# StimFilterV1.net
KiCad netlist of a schematic drawn in EasyEDA Pro
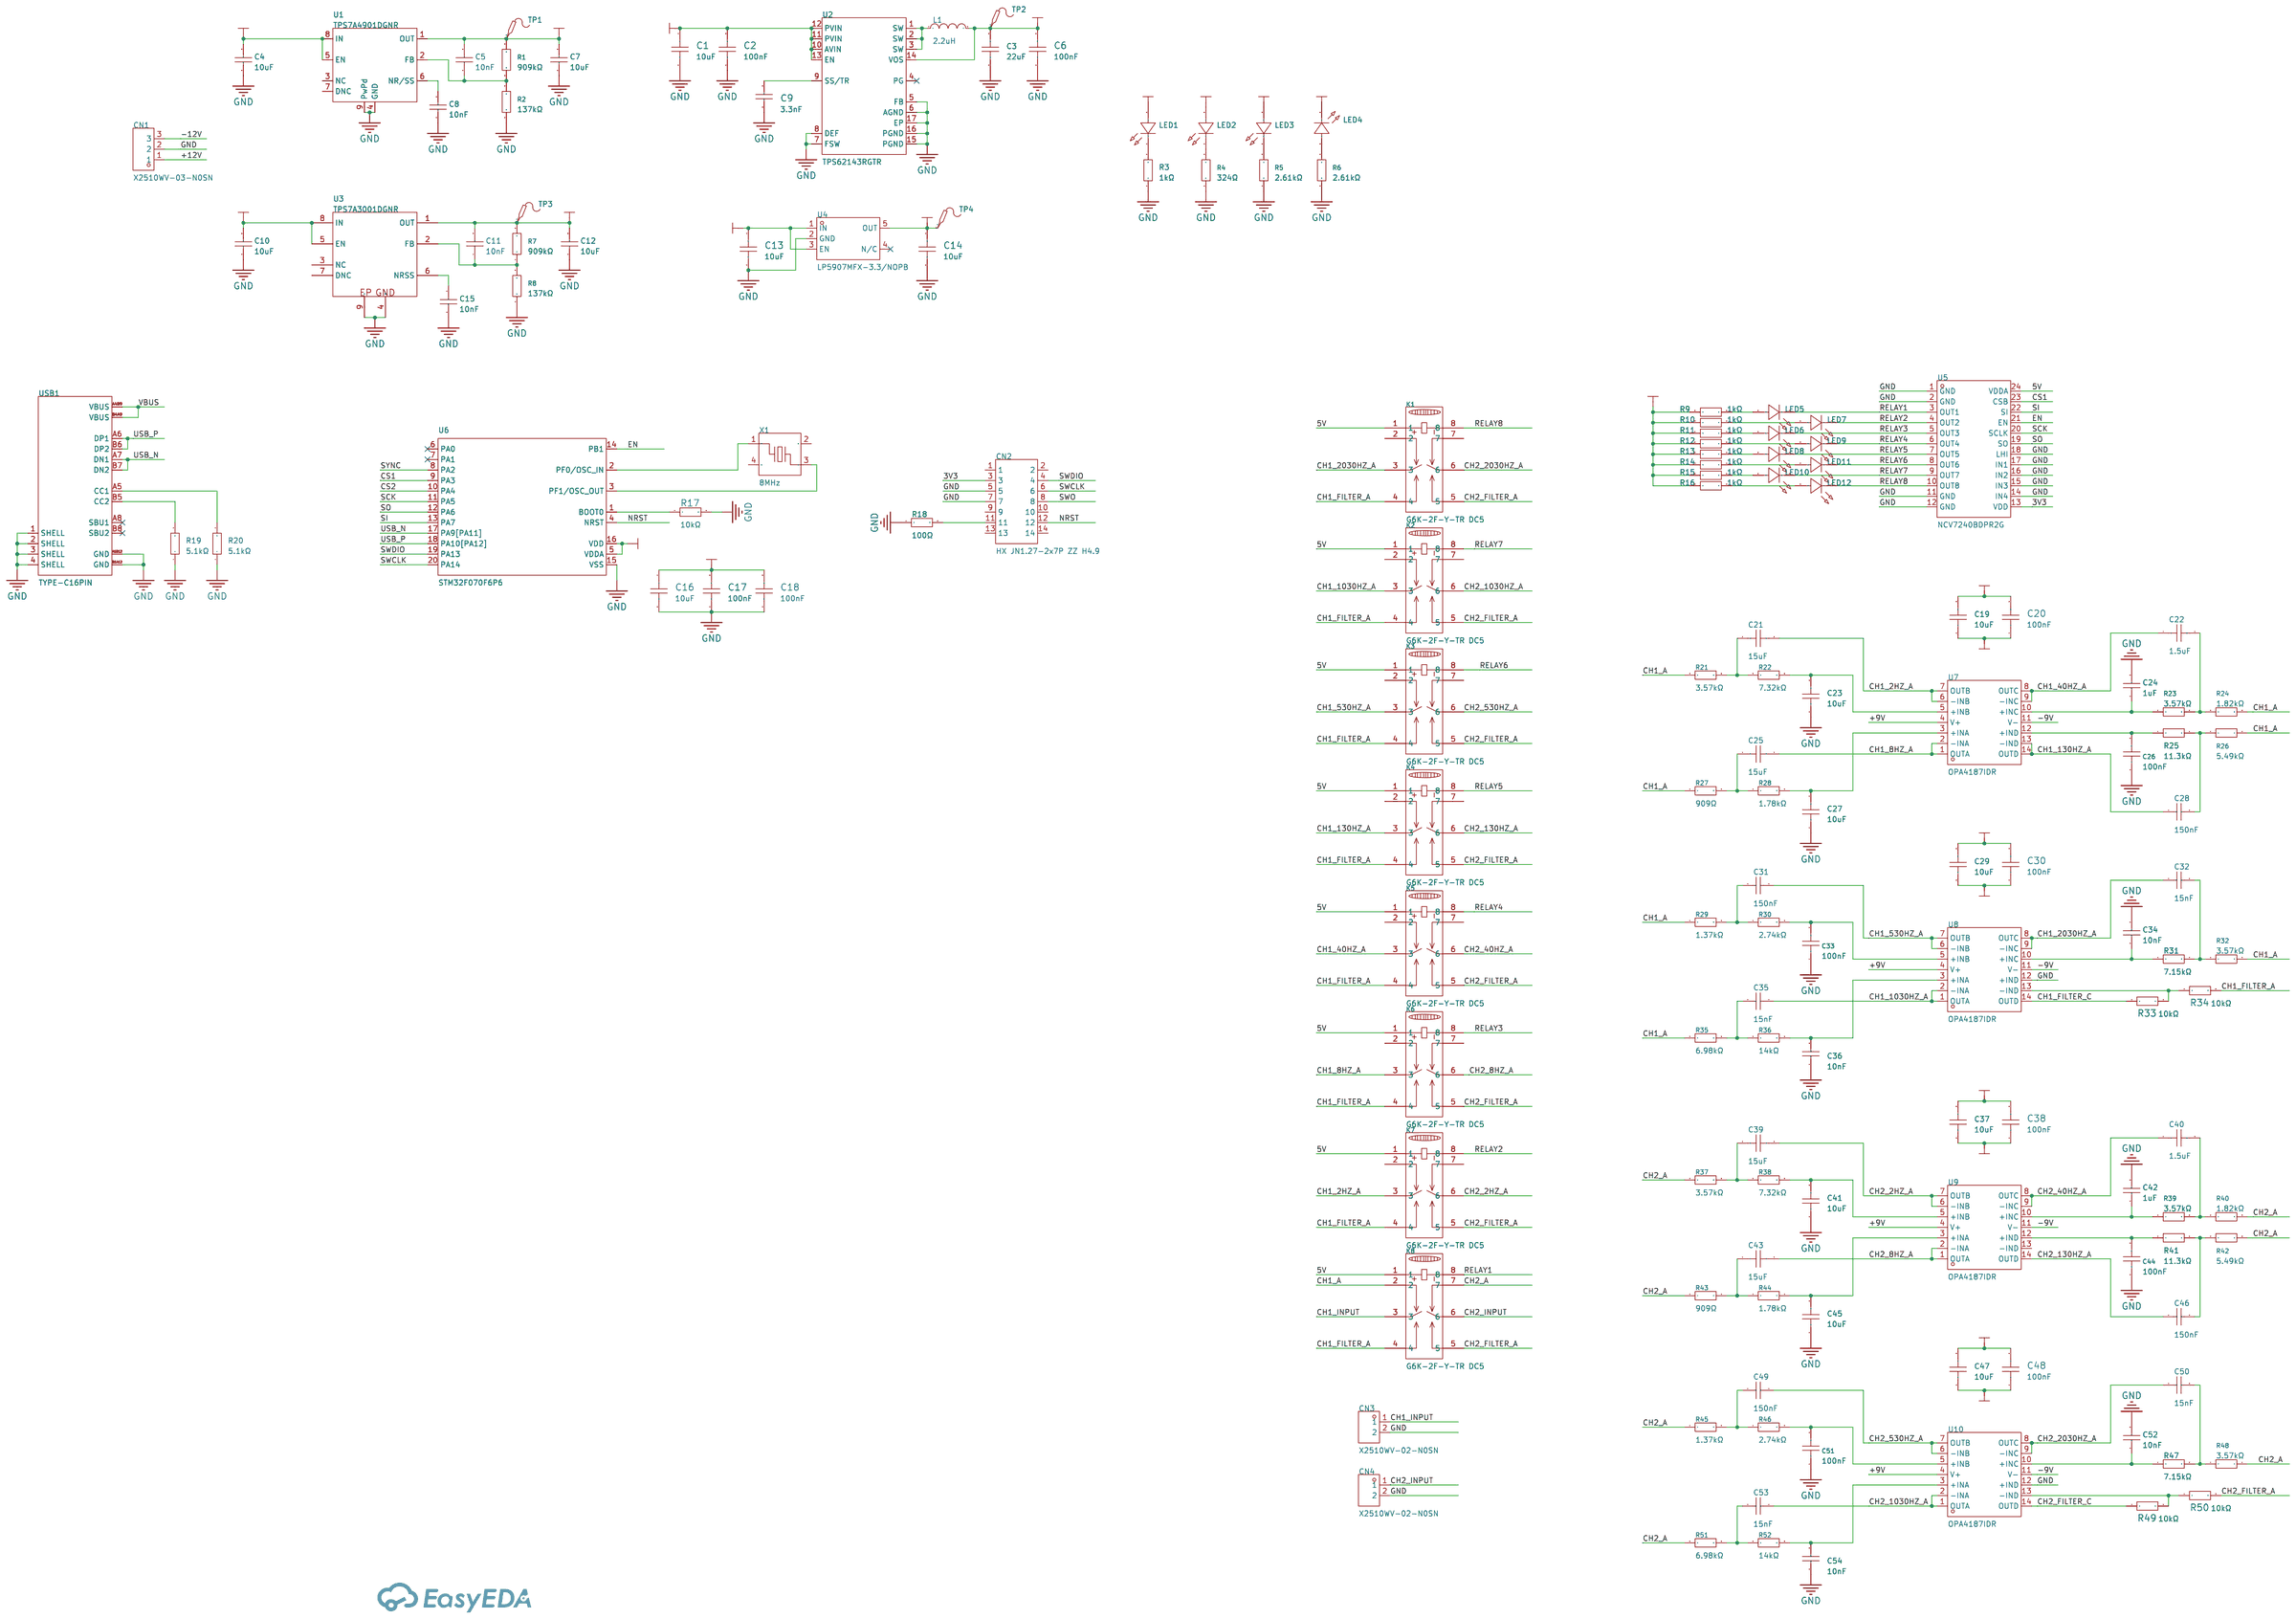
[diagram p0: P1]
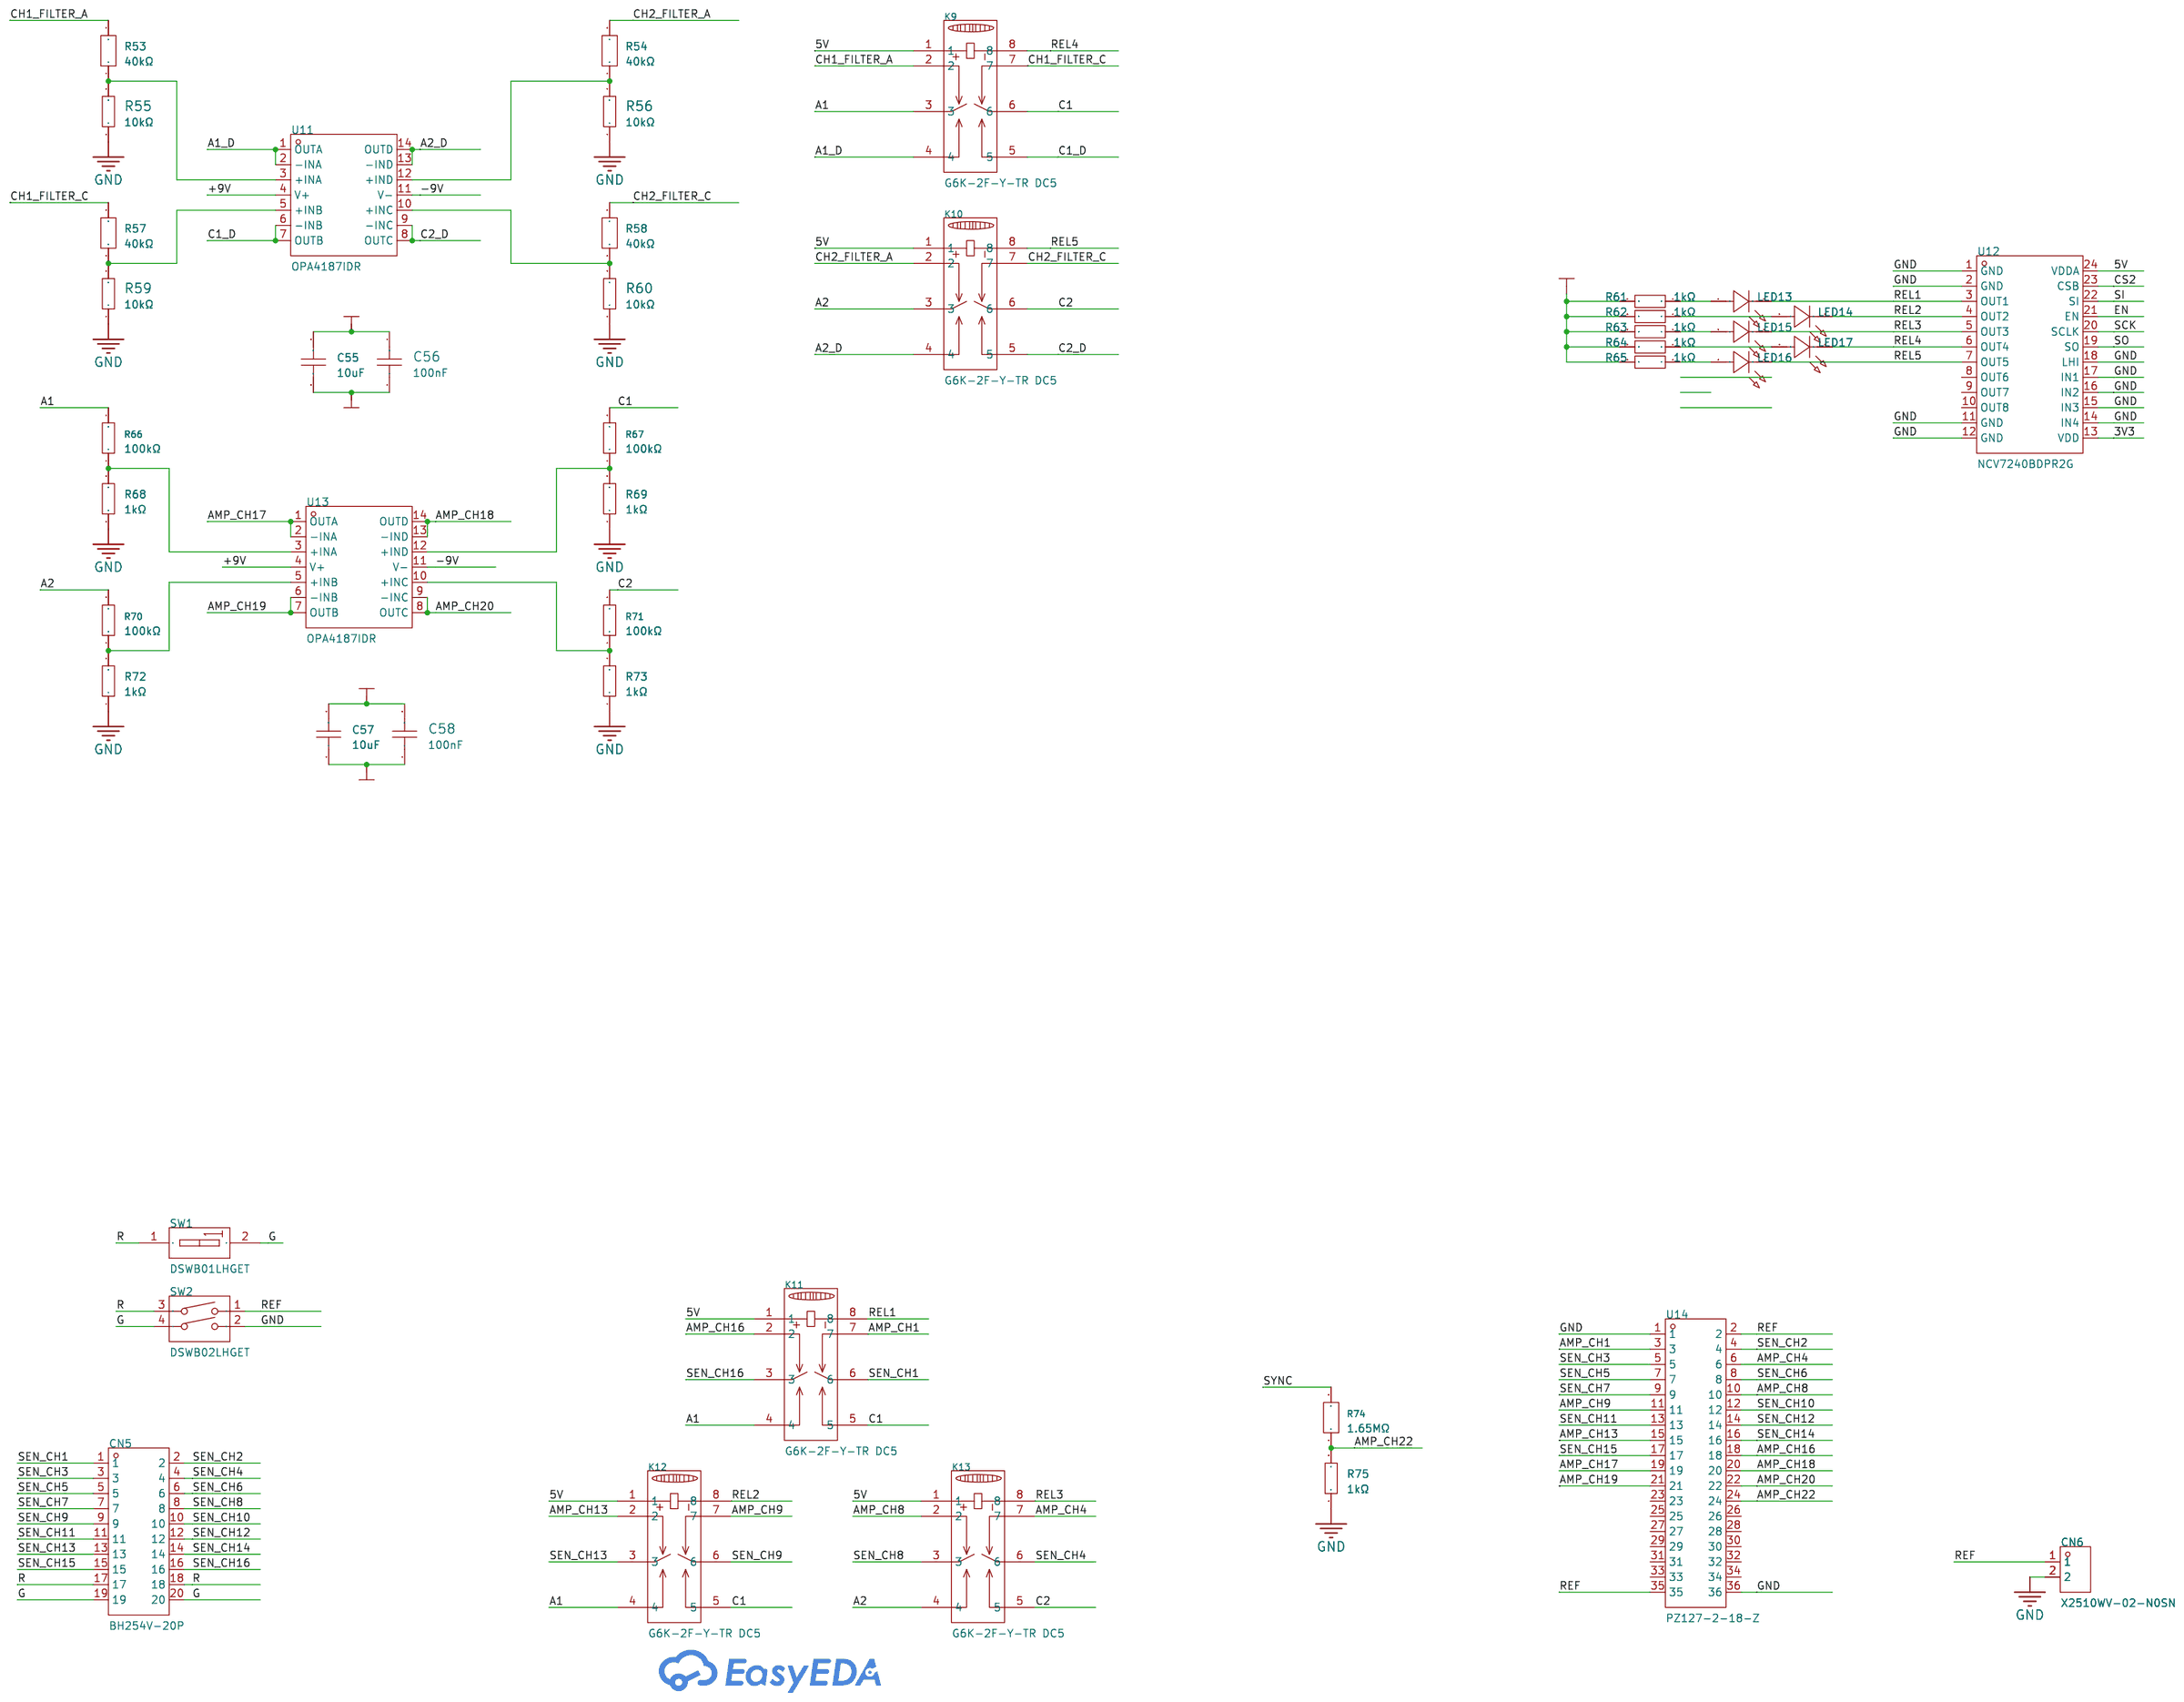
[diagram p1: P2]

(export (version "E")
  (design (tool "Eeschema 10.0.6"))
  (components
    (comp (ref "C1")
      (value "10uF")
      (footprint "easyedapro:C0603")
      (fields
        (field (name "Manufacturer Part") "GRM188R61E106KA73D")
        (field (name "Manufacturer") "muRata(村田)")
      )
      (libsource (lib "easyedapro") (part "GRM188R61E106KA73D"))
    )
    (comp (ref "C2")
      (value "100nF")
      (footprint "easyedapro:C0603")
      (fields
        (field (name "Manufacturer Part") "CC0603KRX7R9BB104")
        (field (name "Manufacturer") "YAGEO(国巨)")
      )
      (libsource (lib "easyedapro") (part "CC0603KRX7R9BB104"))
    )
    (comp (ref "C3")
      (value "22uF")
      (footprint "easyedapro:C0603")
      (fields
        (field (name "Manufacturer Part") "CL10A226MP8NUNE")
        (field (name "Manufacturer") "SAMSUNG(三星)")
      )
      (libsource (lib "easyedapro") (part "CL10A226MP8NUNE"))
    )
    (comp (ref "C4")
      (value "10uF")
      (footprint "easyedapro:C0805")
      (description "Capacitance:10uF Tolerance:±10% Tolerance:±10% Voltage Rating:10V Temperature Coefficient:X7R")
      (fields
        (field (name "Manufacturer Part") "CL21B106KPQNNNE")
        (field (name "Manufacturer") "SAMSUNG(三星)")
      )
      (libsource (lib "easyedapro") (part "CL21B106KPQNNNE"))
    )
    (comp (ref "C5")
      (value "10nF")
      (footprint "easyedapro:C0603")
      (description "Capacitance:10nF Tolerance:±10% Tolerance:±10% Voltage Rating:50V Temperature Coefficient:X7R")
      (fields
        (field (name "Manufacturer Part") "CL10B103KB8NNNC")
        (field (name "Manufacturer") "SAMSUNG(三星)")
      )
      (libsource (lib "easyedapro") (part "CL10B103KB8NNNC"))
    )
    (comp (ref "C6")
      (value "100nF")
      (footprint "easyedapro:C0603")
      (fields
        (field (name "Manufacturer Part") "CC0603KRX7R9BB104")
        (field (name "Manufacturer") "YAGEO(国巨)")
      )
      (libsource (lib "easyedapro") (part "CC0603KRX7R9BB104"))
    )
    (comp (ref "C7")
      (value "10uF")
      (footprint "easyedapro:C0805")
      (description "Capacitance:10uF Tolerance:±10% Tolerance:±10% Voltage Rating:10V Temperature Coefficient:X7R")
      (fields
        (field (name "Manufacturer Part") "CL21B106KPQNNNE")
        (field (name "Manufacturer") "SAMSUNG(三星)")
      )
      (libsource (lib "easyedapro") (part "CL21B106KPQNNNE"))
    )
    (comp (ref "C8")
      (value "10nF")
      (footprint "easyedapro:C0603")
      (description "Capacitance:10nF Tolerance:±10% Tolerance:±10% Voltage Rating:50V Temperature Coefficient:X7R")
      (fields
        (field (name "Manufacturer Part") "CL10B103KB8NNNC")
        (field (name "Manufacturer") "SAMSUNG(三星)")
      )
      (libsource (lib "easyedapro") (part "CL10B103KB8NNNC"))
    )
    (comp (ref "C9")
      (value "3.3nF")
      (footprint "easyedapro:C0603")
      (fields
        (field (name "Manufacturer Part") "CC0603KRX7R9BB332")
        (field (name "Manufacturer") "YAGEO(国巨)")
      )
      (libsource (lib "easyedapro") (part "CC0603KRX7R9BB332"))
    )
    (comp (ref "C10")
      (value "10uF")
      (footprint "easyedapro:C0805")
      (description "Capacitance:10uF Tolerance:±10% Tolerance:±10% Voltage Rating:10V Temperature Coefficient:X7R")
      (fields
        (field (name "Manufacturer Part") "CL21B106KPQNNNE")
        (field (name "Manufacturer") "SAMSUNG(三星)")
      )
      (libsource (lib "easyedapro") (part "CL21B106KPQNNNE"))
    )
    (comp (ref "C11")
      (value "10nF")
      (footprint "easyedapro:C0603")
      (description "Capacitance:10nF Tolerance:±10% Tolerance:±10% Voltage Rating:50V Temperature Coefficient:X7R")
      (fields
        (field (name "Manufacturer Part") "CL10B103KB8NNNC")
        (field (name "Manufacturer") "SAMSUNG(三星)")
      )
      (libsource (lib "easyedapro") (part "CL10B103KB8NNNC"))
    )
    (comp (ref "C12")
      (value "10uF")
      (footprint "easyedapro:C0805")
      (description "Capacitance:10uF Tolerance:±10% Tolerance:±10% Voltage Rating:10V Temperature Coefficient:X7R")
      (fields
        (field (name "Manufacturer Part") "CL21B106KPQNNNE")
        (field (name "Manufacturer") "SAMSUNG(三星)")
      )
      (libsource (lib "easyedapro") (part "CL21B106KPQNNNE"))
    )
    (comp (ref "C13")
      (value "10uF")
      (footprint "easyedapro:C0603")
      (fields
        (field (name "Manufacturer Part") "GRM188R61E106KA73D")
        (field (name "Manufacturer") "muRata(村田)")
      )
      (libsource (lib "easyedapro") (part "GRM188R61E106KA73D"))
    )
    (comp (ref "C14")
      (value "10uF")
      (footprint "easyedapro:C0603")
      (fields
        (field (name "Manufacturer Part") "GRM188R61E106KA73D")
        (field (name "Manufacturer") "muRata(村田)")
      )
      (libsource (lib "easyedapro") (part "GRM188R61E106KA73D"))
    )
    (comp (ref "C15")
      (value "10nF")
      (footprint "easyedapro:C0603")
      (description "Capacitance:10nF Tolerance:±10% Tolerance:±10% Voltage Rating:50V Temperature Coefficient:X7R")
      (fields
        (field (name "Manufacturer Part") "CL10B103KB8NNNC")
        (field (name "Manufacturer") "SAMSUNG(三星)")
      )
      (libsource (lib "easyedapro") (part "CL10B103KB8NNNC"))
    )
    (comp (ref "C16")
      (value "10uF")
      (footprint "easyedapro:C0603")
      (fields
        (field (name "Manufacturer Part") "GRM188R61E106KA73D")
        (field (name "Manufacturer") "muRata(村田)")
      )
      (libsource (lib "easyedapro") (part "GRM188R61E106KA73D"))
    )
    (comp (ref "C17")
      (value "100nF")
      (footprint "easyedapro:C0603")
      (fields
        (field (name "Manufacturer Part") "CC0603KRX7R9BB104")
        (field (name "Manufacturer") "YAGEO(国巨)")
      )
      (libsource (lib "easyedapro") (part "CC0603KRX7R9BB104"))
    )
    (comp (ref "C18")
      (value "100nF")
      (footprint "easyedapro:C0603")
      (fields
        (field (name "Manufacturer Part") "CC0603KRX7R9BB104")
        (field (name "Manufacturer") "YAGEO(国巨)")
      )
      (libsource (lib "easyedapro") (part "CC0603KRX7R9BB104"))
    )
    (comp (ref "C19")
      (value "10uF")
      (footprint "easyedapro:C0805")
      (description "Capacitance:10uF Tolerance:±10% Tolerance:±10% Voltage Rating:25V Temperature Coefficient:X5R")
      (fields
        (field (name "Manufacturer Part") "CL21A106KAYNNNE")
        (field (name "Manufacturer") "SAMSUNG(三星)")
      )
      (libsource (lib "easyedapro") (part "CL21A106KAYNNNE"))
    )
    (comp (ref "C20")
      (value "100nF")
      (footprint "easyedapro:C0603")
      (fields
        (field (name "Manufacturer Part") "CC0603KRX7R9BB104")
        (field (name "Manufacturer") "YAGEO(国巨)")
      )
      (libsource (lib "easyedapro") (part "CC0603KRX7R9BB104"))
    )
    (comp (ref "C21")
      (value "15uF")
      (footprint "easyedapro:C0603")
      (description "Capacitance:15uF Tolerance:±20% Tolerance:±20% Voltage Rating:6.3V Temperature Coefficient:X5R")
      (fields (field (name "Manufacturer Part") "C1608X5R0J156MT000E") (field (name "Manufacturer") "TDK"))
      (libsource (lib "easyedapro") (part "C1608X5R0J156MT000E"))
    )
    (comp (ref "C22")
      (value "1.5uF")
      (footprint "easyedapro:C0603")
      (description "Capacitance:1.5uF Tolerance:±10% Tolerance:±10% Voltage Rating:10V Temperature Coefficient:X7R")
      (fields (field (name "Manufacturer Part") "C1608X7R1A155KT000E") (field (name "Manufacturer") "TDK"))
      (libsource (lib "easyedapro") (part "C1608X7R1A155KT000E"))
    )
    (comp (ref "C23")
      (value "10uF")
      (footprint "easyedapro:C0603")
      (description "Capacitance:10uF Tolerance:±10% Tolerance:±10% Voltage Rating:10V Temperature Coefficient:X5R")
      (fields
        (field (name "Manufacturer Part") "CL10A106KP8NNNC")
        (field (name "Manufacturer") "SAMSUNG(三星)")
      )
      (libsource (lib "easyedapro") (part "CL10A106KP8NNNC"))
    )
    (comp (ref "C24")
      (value "1uF")
      (footprint "easyedapro:C0603")
      (description "Capacitance:1uF Tolerance:±10% Tolerance:±10% Voltage Rating:16V Temperature Coefficient:X5R")
      (fields
        (field (name "Manufacturer Part") "CL10A105KO8NNNC")
        (field (name "Manufacturer") "SAMSUNG(三星)")
      )
      (libsource (lib "easyedapro") (part "CL10A105KO8NNNC"))
    )
    (comp (ref "C25")
      (value "15uF")
      (footprint "easyedapro:C0603")
      (description "Capacitance:15uF Tolerance:±20% Tolerance:±20% Voltage Rating:6.3V Temperature Coefficient:X5R")
      (fields (field (name "Manufacturer Part") "C1608X5R0J156MT000E") (field (name "Manufacturer") "TDK"))
      (libsource (lib "easyedapro") (part "C1608X5R0J156MT000E"))
    )
    (comp (ref "C26")
      (value "100nF")
      (footprint "easyedapro:C0603")
      (description "Capacitance:100nF Tolerance:±10% Tolerance:±10% Voltage Rating:50V Temperature Coefficient:X7R")
      (fields
        (field (name "Manufacturer Part") "CL10B104KB8NNNC")
        (field (name "Manufacturer") "SAMSUNG(三星)")
      )
      (libsource (lib "easyedapro") (part "CL10B104KB8NNNC"))
    )
    (comp (ref "C27")
      (value "10uF")
      (footprint "easyedapro:C0603")
      (description "Capacitance:10uF Tolerance:±10% Tolerance:±10% Voltage Rating:10V Temperature Coefficient:X5R")
      (fields
        (field (name "Manufacturer Part") "CL10A106KP8NNNC")
        (field (name "Manufacturer") "SAMSUNG(三星)")
      )
      (libsource (lib "easyedapro") (part "CL10A106KP8NNNC"))
    )
    (comp (ref "C28")
      (value "150nF")
      (footprint "easyedapro:C0603")
      (description "Capacitance:150nF Tolerance:±10% Tolerance:±10% Voltage Rating:50V Temperature Coefficient:X7R")
      (fields (field (name "Manufacturer Part") "0603B154K500NT") (field (name "Manufacturer") "FH(风华)"))
      (libsource (lib "easyedapro") (part "0603B154K500NT"))
    )
    (comp (ref "C29")
      (value "10uF")
      (footprint "easyedapro:C0805")
      (description "Capacitance:10uF Tolerance:±10% Tolerance:±10% Voltage Rating:25V Temperature Coefficient:X5R")
      (fields
        (field (name "Manufacturer Part") "CL21A106KAYNNNE")
        (field (name "Manufacturer") "SAMSUNG(三星)")
      )
      (libsource (lib "easyedapro") (part "CL21A106KAYNNNE"))
    )
    (comp (ref "C30")
      (value "100nF")
      (footprint "easyedapro:C0603")
      (fields
        (field (name "Manufacturer Part") "CC0603KRX7R9BB104")
        (field (name "Manufacturer") "YAGEO(国巨)")
      )
      (libsource (lib "easyedapro") (part "CC0603KRX7R9BB104"))
    )
    (comp (ref "C31")
      (value "150nF")
      (footprint "easyedapro:C0603")
      (description "Capacitance:150nF Tolerance:±10% Tolerance:±10% Voltage Rating:50V Temperature Coefficient:X7R")
      (fields (field (name "Manufacturer Part") "0603B154K500NT") (field (name "Manufacturer") "FH(风华)"))
      (libsource (lib "easyedapro") (part "0603B154K500NT"))
    )
    (comp (ref "C32")
      (value "15nF")
      (footprint "easyedapro:C0603")
      (description "Capacitance:15nF Tolerance:±10% Tolerance:±10% Voltage Rating:50V Temperature Coefficient:X7R")
      (fields (field (name "Manufacturer Part") "0603B153K500NT") (field (name "Manufacturer") "FH(风华)"))
      (libsource (lib "easyedapro") (part "0603B153K500NT"))
    )
    (comp (ref "C33")
      (value "100nF")
      (footprint "easyedapro:C0603")
      (description "Capacitance:100nF Tolerance:±10% Tolerance:±10% Voltage Rating:50V Temperature Coefficient:X7R")
      (fields
        (field (name "Manufacturer Part") "CL10B104KB8NNNC")
        (field (name "Manufacturer") "SAMSUNG(三星)")
      )
      (libsource (lib "easyedapro") (part "CL10B104KB8NNNC"))
    )
    (comp (ref "C34")
      (value "10nF")
      (footprint "easyedapro:C0603")
      (description "Capacitance:10nF Tolerance:±10% Tolerance:±10% Voltage Rating:50V Temperature Coefficient:X7R")
      (fields
        (field (name "Manufacturer Part") "CL10B103KB8NNNC")
        (field (name "Manufacturer") "SAMSUNG(三星)")
      )
      (libsource (lib "easyedapro") (part "CL10B103KB8NNNC"))
    )
    (comp (ref "C35")
      (value "15nF")
      (footprint "easyedapro:C0603")
      (description "Capacitance:15nF Tolerance:±10% Tolerance:±10% Voltage Rating:50V Temperature Coefficient:X7R")
      (fields (field (name "Manufacturer Part") "0603B153K500NT") (field (name "Manufacturer") "FH(风华)"))
      (libsource (lib "easyedapro") (part "0603B153K500NT"))
    )
    (comp (ref "C36")
      (value "10nF")
      (footprint "easyedapro:C0603")
      (description "Capacitance:10nF Tolerance:±10% Tolerance:±10% Voltage Rating:50V Temperature Coefficient:X7R")
      (fields
        (field (name "Manufacturer Part") "CL10B103KB8NNNC")
        (field (name "Manufacturer") "SAMSUNG(三星)")
      )
      (libsource (lib "easyedapro") (part "CL10B103KB8NNNC"))
    )
    (comp (ref "C37")
      (value "10uF")
      (footprint "easyedapro:C0805")
      (description "Capacitance:10uF Tolerance:±10% Tolerance:±10% Voltage Rating:25V Temperature Coefficient:X5R")
      (fields
        (field (name "Manufacturer Part") "CL21A106KAYNNNE")
        (field (name "Manufacturer") "SAMSUNG(三星)")
      )
      (libsource (lib "easyedapro") (part "CL21A106KAYNNNE"))
    )
    (comp (ref "C38")
      (value "100nF")
      (footprint "easyedapro:C0603")
      (fields
        (field (name "Manufacturer Part") "CC0603KRX7R9BB104")
        (field (name "Manufacturer") "YAGEO(国巨)")
      )
      (libsource (lib "easyedapro") (part "CC0603KRX7R9BB104"))
    )
    (comp (ref "C39")
      (value "15uF")
      (footprint "easyedapro:C0603")
      (description "Capacitance:15uF Tolerance:±20% Tolerance:±20% Voltage Rating:6.3V Temperature Coefficient:X5R")
      (fields (field (name "Manufacturer Part") "C1608X5R0J156MT000E") (field (name "Manufacturer") "TDK"))
      (libsource (lib "easyedapro") (part "C1608X5R0J156MT000E"))
    )
    (comp (ref "C40")
      (value "1.5uF")
      (footprint "easyedapro:C0603")
      (description "Capacitance:1.5uF Tolerance:±10% Tolerance:±10% Voltage Rating:10V Temperature Coefficient:X7R")
      (fields (field (name "Manufacturer Part") "C1608X7R1A155KT000E") (field (name "Manufacturer") "TDK"))
      (libsource (lib "easyedapro") (part "C1608X7R1A155KT000E"))
    )
    (comp (ref "C41")
      (value "10uF")
      (footprint "easyedapro:C0603")
      (description "Capacitance:10uF Tolerance:±10% Tolerance:±10% Voltage Rating:10V Temperature Coefficient:X5R")
      (fields
        (field (name "Manufacturer Part") "CL10A106KP8NNNC")
        (field (name "Manufacturer") "SAMSUNG(三星)")
      )
      (libsource (lib "easyedapro") (part "CL10A106KP8NNNC"))
    )
    (comp (ref "C42")
      (value "1uF")
      (footprint "easyedapro:C0603")
      (description "Capacitance:1uF Tolerance:±10% Tolerance:±10% Voltage Rating:16V Temperature Coefficient:X5R")
      (fields
        (field (name "Manufacturer Part") "CL10A105KO8NNNC")
        (field (name "Manufacturer") "SAMSUNG(三星)")
      )
      (libsource (lib "easyedapro") (part "CL10A105KO8NNNC"))
    )
    (comp (ref "C43")
      (value "15uF")
      (footprint "easyedapro:C0603")
      (description "Capacitance:15uF Tolerance:±20% Tolerance:±20% Voltage Rating:6.3V Temperature Coefficient:X5R")
      (fields (field (name "Manufacturer Part") "C1608X5R0J156MT000E") (field (name "Manufacturer") "TDK"))
      (libsource (lib "easyedapro") (part "C1608X5R0J156MT000E"))
    )
    (comp (ref "C44")
      (value "100nF")
      (footprint "easyedapro:C0603")
      (description "Capacitance:100nF Tolerance:±10% Tolerance:±10% Voltage Rating:50V Temperature Coefficient:X7R")
      (fields
        (field (name "Manufacturer Part") "CL10B104KB8NNNC")
        (field (name "Manufacturer") "SAMSUNG(三星)")
      )
      (libsource (lib "easyedapro") (part "CL10B104KB8NNNC"))
    )
    (comp (ref "C45")
      (value "10uF")
      (footprint "easyedapro:C0603")
      (description "Capacitance:10uF Tolerance:±10% Tolerance:±10% Voltage Rating:10V Temperature Coefficient:X5R")
      (fields
        (field (name "Manufacturer Part") "CL10A106KP8NNNC")
        (field (name "Manufacturer") "SAMSUNG(三星)")
      )
      (libsource (lib "easyedapro") (part "CL10A106KP8NNNC"))
    )
    (comp (ref "C46")
      (value "150nF")
      (footprint "easyedapro:C0603")
      (description "Capacitance:150nF Tolerance:±10% Tolerance:±10% Voltage Rating:50V Temperature Coefficient:X7R")
      (fields (field (name "Manufacturer Part") "0603B154K500NT") (field (name "Manufacturer") "FH(风华)"))
      (libsource (lib "easyedapro") (part "0603B154K500NT"))
    )
    (comp (ref "C47")
      (value "10uF")
      (footprint "easyedapro:C0805")
      (description "Capacitance:10uF Tolerance:±10% Tolerance:±10% Voltage Rating:25V Temperature Coefficient:X5R")
      (fields
        (field (name "Manufacturer Part") "CL21A106KAYNNNE")
        (field (name "Manufacturer") "SAMSUNG(三星)")
      )
      (libsource (lib "easyedapro") (part "CL21A106KAYNNNE"))
    )
    (comp (ref "C48")
      (value "100nF")
      (footprint "easyedapro:C0603")
      (fields
        (field (name "Manufacturer Part") "CC0603KRX7R9BB104")
        (field (name "Manufacturer") "YAGEO(国巨)")
      )
      (libsource (lib "easyedapro") (part "CC0603KRX7R9BB104"))
    )
    (comp (ref "C49")
      (value "150nF")
      (footprint "easyedapro:C0603")
      (description "Capacitance:150nF Tolerance:±10% Tolerance:±10% Voltage Rating:50V Temperature Coefficient:X7R")
      (fields (field (name "Manufacturer Part") "0603B154K500NT") (field (name "Manufacturer") "FH(风华)"))
      (libsource (lib "easyedapro") (part "0603B154K500NT"))
    )
    (comp (ref "C50")
      (value "15nF")
      (footprint "easyedapro:C0603")
      (description "Capacitance:15nF Tolerance:±10% Tolerance:±10% Voltage Rating:50V Temperature Coefficient:X7R")
      (fields (field (name "Manufacturer Part") "0603B153K500NT") (field (name "Manufacturer") "FH(风华)"))
      (libsource (lib "easyedapro") (part "0603B153K500NT"))
    )
    (comp (ref "C51")
      (value "100nF")
      (footprint "easyedapro:C0603")
      (description "Capacitance:100nF Tolerance:±10% Tolerance:±10% Voltage Rating:50V Temperature Coefficient:X7R")
      (fields
        (field (name "Manufacturer Part") "CL10B104KB8NNNC")
        (field (name "Manufacturer") "SAMSUNG(三星)")
      )
      (libsource (lib "easyedapro") (part "CL10B104KB8NNNC"))
    )
    (comp (ref "C52")
      (value "10nF")
      (footprint "easyedapro:C0603")
      (description "Capacitance:10nF Tolerance:±10% Tolerance:±10% Voltage Rating:50V Temperature Coefficient:X7R")
      (fields
        (field (name "Manufacturer Part") "CL10B103KB8NNNC")
        (field (name "Manufacturer") "SAMSUNG(三星)")
      )
      (libsource (lib "easyedapro") (part "CL10B103KB8NNNC"))
    )
    (comp (ref "C53")
      (value "15nF")
      (footprint "easyedapro:C0603")
      (description "Capacitance:15nF Tolerance:±10% Tolerance:±10% Voltage Rating:50V Temperature Coefficient:X7R")
      (fields (field (name "Manufacturer Part") "0603B153K500NT") (field (name "Manufacturer") "FH(风华)"))
      (libsource (lib "easyedapro") (part "0603B153K500NT"))
    )
    (comp (ref "C54")
      (value "10nF")
      (footprint "easyedapro:C0603")
      (description "Capacitance:10nF Tolerance:±10% Tolerance:±10% Voltage Rating:50V Temperature Coefficient:X7R")
      (fields
        (field (name "Manufacturer Part") "CL10B103KB8NNNC")
        (field (name "Manufacturer") "SAMSUNG(三星)")
      )
      (libsource (lib "easyedapro") (part "CL10B103KB8NNNC"))
    )
    (comp (ref "CN1")
      (value "X2510WV-03-N0SN")
      (footprint "easyedapro:CONN-TH_3P-X2510WV-0X-N0SN")
      (fields (field (name "Manufacturer") "XKB Connection(中国星坤)"))
      (libsource (lib "easyedapro") (part "X2510WV-03-N0SN"))
    )
    (comp (ref "CN2")
      (value "HX JN1.27-2x7P ZZ H4.9")
      (footprint "easyedapro:IDC-TH_14P-P1.27_C42455940")
      (fields (field (name "Manufacturer") "hanxia(韩下)"))
      (libsource (lib "easyedapro") (part "HX JN1.27-2X7P ZZ H4.9"))
    )
    (comp (ref "CN3")
      (value "X2510WV-02-N0SN")
      (footprint "easyedapro:CONN-TH_2P-X2510WV-02-N0SN")
      (fields (field (name "Manufacturer") "XKB Connection(中国星坤)"))
      (libsource (lib "easyedapro") (part "X2510WV-02-N0SN"))
    )
    (comp (ref "CN4")
      (value "X2510WV-02-N0SN")
      (footprint "easyedapro:CONN-TH_2P-X2510WV-02-N0SN")
      (fields (field (name "Manufacturer") "XKB Connection(中国星坤)"))
      (libsource (lib "easyedapro") (part "X2510WV-02-N0SN"))
    )
    (comp (ref "K1")
      (value "G6K-2F-Y-TR DC5")
      (footprint "easyedapro:RELAY-SMD_G6K-2F-X-XX")
      (fields (field (name "Manufacturer") "OMRON(欧姆龙)"))
      (libsource (lib "easyedapro") (part "G6K-2F-Y-DC5"))
    )
    (comp (ref "K2")
      (value "G6K-2F-Y-TR DC5")
      (footprint "easyedapro:RELAY-SMD_G6K-2F-X-XX")
      (fields (field (name "Manufacturer") "OMRON(欧姆龙)"))
      (libsource (lib "easyedapro") (part "G6K-2F-Y-DC5"))
    )
    (comp (ref "K3")
      (value "G6K-2F-Y-TR DC5")
      (footprint "easyedapro:RELAY-SMD_G6K-2F-X-XX")
      (fields (field (name "Manufacturer") "OMRON(欧姆龙)"))
      (libsource (lib "easyedapro") (part "G6K-2F-Y-DC5"))
    )
    (comp (ref "K4")
      (value "G6K-2F-Y-TR DC5")
      (footprint "easyedapro:RELAY-SMD_G6K-2F-X-XX")
      (fields (field (name "Manufacturer") "OMRON(欧姆龙)"))
      (libsource (lib "easyedapro") (part "G6K-2F-Y-DC5"))
    )
    (comp (ref "K5")
      (value "G6K-2F-Y-TR DC5")
      (footprint "easyedapro:RELAY-SMD_G6K-2F-X-XX")
      (fields (field (name "Manufacturer") "OMRON(欧姆龙)"))
      (libsource (lib "easyedapro") (part "G6K-2F-Y-DC5"))
    )
    (comp (ref "K6")
      (value "G6K-2F-Y-TR DC5")
      (footprint "easyedapro:RELAY-SMD_G6K-2F-X-XX")
      (fields (field (name "Manufacturer") "OMRON(欧姆龙)"))
      (libsource (lib "easyedapro") (part "G6K-2F-Y-DC5"))
    )
    (comp (ref "K7")
      (value "G6K-2F-Y-TR DC5")
      (footprint "easyedapro:RELAY-SMD_G6K-2F-X-XX")
      (fields (field (name "Manufacturer") "OMRON(欧姆龙)"))
      (libsource (lib "easyedapro") (part "G6K-2F-Y-DC5"))
    )
    (comp (ref "K8")
      (value "G6K-2F-Y-TR DC5")
      (footprint "easyedapro:RELAY-SMD_G6K-2F-X-XX")
      (fields (field (name "Manufacturer") "OMRON(欧姆龙)"))
      (libsource (lib "easyedapro") (part "G6K-2F-Y-DC5"))
    )
    (comp (ref "L1")
      (value "2.2uH")
      (footprint "easyedapro:L0806")
      (fields (field (name "Manufacturer Part") "TFM201610ALM-2R2MTAA") (field (name "Manufacturer") "TDK"))
      (libsource (lib "easyedapro") (part "TFM201610ALM-2R2MTAA"))
    )
    (comp (ref "LED1")
      (value "A-SP192DGHC-C01-4T")
      (footprint "easyedapro:LED0603-FD")
      (fields (field (name "Manufacturer") "Amicc(欧密格光电)"))
      (libsource (lib "easyedapro") (part "A-SP192DGHC-C01-4T"))
    )
    (comp (ref "LED2")
      (value "A-SP192DGHC-C01-4T")
      (footprint "easyedapro:LED0603-FD")
      (fields (field (name "Manufacturer") "Amicc(欧密格光电)"))
      (libsource (lib "easyedapro") (part "A-SP192DGHC-C01-4T"))
    )
    (comp (ref "LED3")
      (value "A-SP192DGHC-C01-4T")
      (footprint "easyedapro:LED0603-FD")
      (fields (field (name "Manufacturer") "Amicc(欧密格光电)"))
      (libsource (lib "easyedapro") (part "A-SP192DGHC-C01-4T"))
    )
    (comp (ref "LED4")
      (value "A-SP192DGHC-C01-4T")
      (footprint "easyedapro:LED0603-FD")
      (fields (field (name "Manufacturer") "Amicc(欧密格光电)"))
      (libsource (lib "easyedapro") (part "A-SP192DGHC-C01-4T"))
    )
    (comp (ref "LED5")
      (value "A-SP192DGHC-C01-4T")
      (footprint "easyedapro:LED0603-FD")
      (fields (field (name "Manufacturer") "Amicc(欧密格光电)"))
      (libsource (lib "easyedapro") (part "A-SP192DGHC-C01-4T"))
    )
    (comp (ref "LED6")
      (value "A-SP192DGHC-C01-4T")
      (footprint "easyedapro:LED0603-FD")
      (fields (field (name "Manufacturer") "Amicc(欧密格光电)"))
      (libsource (lib "easyedapro") (part "A-SP192DGHC-C01-4T"))
    )
    (comp (ref "LED7")
      (value "A-SP192DGHC-C01-4T")
      (footprint "easyedapro:LED0603-FD")
      (fields (field (name "Manufacturer") "Amicc(欧密格光电)"))
      (libsource (lib "easyedapro") (part "A-SP192DGHC-C01-4T"))
    )
    (comp (ref "LED8")
      (value "A-SP192DGHC-C01-4T")
      (footprint "easyedapro:LED0603-FD")
      (fields (field (name "Manufacturer") "Amicc(欧密格光电)"))
      (libsource (lib "easyedapro") (part "A-SP192DGHC-C01-4T"))
    )
    (comp (ref "LED9")
      (value "A-SP192DGHC-C01-4T")
      (footprint "easyedapro:LED0603-FD")
      (fields (field (name "Manufacturer") "Amicc(欧密格光电)"))
      (libsource (lib "easyedapro") (part "A-SP192DGHC-C01-4T"))
    )
    (comp (ref "LED10")
      (value "A-SP192DGHC-C01-4T")
      (footprint "easyedapro:LED0603-FD")
      (fields (field (name "Manufacturer") "Amicc(欧密格光电)"))
      (libsource (lib "easyedapro") (part "A-SP192DGHC-C01-4T"))
    )
    (comp (ref "LED11")
      (value "A-SP192DGHC-C01-4T")
      (footprint "easyedapro:LED0603-FD")
      (fields (field (name "Manufacturer") "Amicc(欧密格光电)"))
      (libsource (lib "easyedapro") (part "A-SP192DGHC-C01-4T"))
    )
    (comp (ref "LED12")
      (value "A-SP192DGHC-C01-4T")
      (footprint "easyedapro:LED0603-FD")
      (fields (field (name "Manufacturer") "Amicc(欧密格光电)"))
      (libsource (lib "easyedapro") (part "A-SP192DGHC-C01-4T"))
    )
    (comp (ref "R1")
      (value "909kΩ")
      (footprint "easyedapro:R0603")
      (fields
        (field (name "Manufacturer Part") "0603WAF9093T5E")
        (field (name "Manufacturer") "UNI-ROYAL(厚声)")
      )
      (libsource (lib "easyedapro") (part "0603WAF9093T5E"))
    )
    (comp (ref "R2")
      (value "137kΩ")
      (footprint "easyedapro:R0603")
      (fields
        (field (name "Manufacturer Part") "0603WAF1373T5E")
        (field (name "Manufacturer") "UNI-ROYAL(厚声)")
      )
      (libsource (lib "easyedapro") (part "0603WAF1373T5E"))
    )
    (comp (ref "R3")
      (value "1kΩ")
      (footprint "easyedapro:R0603")
      (fields
        (field (name "Manufacturer Part") "0603WAF1001T5E")
        (field (name "Manufacturer") "UNI-ROYAL(厚声)")
      )
      (libsource (lib "easyedapro") (part "0603WAF1001T5E"))
    )
    (comp (ref "R4")
      (value "324Ω")
      (footprint "easyedapro:R0603")
      (fields (field (name "Manufacturer Part") "RTT033240FTP") (field (name "Manufacturer") "RALEC(旺诠)"))
      (libsource (lib "easyedapro") (part "RTT033240FTP"))
    )
    (comp (ref "R5")
      (value "2.61kΩ")
      (footprint "easyedapro:R0603")
      (fields
        (field (name "Manufacturer Part") "0603WAF2611T5E")
        (field (name "Manufacturer") "UNI-ROYAL(厚声)")
      )
      (libsource (lib "easyedapro") (part "0603WAF2611T5E"))
    )
    (comp (ref "R6")
      (value "2.61kΩ")
      (footprint "easyedapro:R0603")
      (fields
        (field (name "Manufacturer Part") "0603WAF2611T5E")
        (field (name "Manufacturer") "UNI-ROYAL(厚声)")
      )
      (libsource (lib "easyedapro") (part "0603WAF2611T5E"))
    )
    (comp (ref "R7")
      (value "909kΩ")
      (footprint "easyedapro:R0603")
      (fields
        (field (name "Manufacturer Part") "0603WAF9093T5E")
        (field (name "Manufacturer") "UNI-ROYAL(厚声)")
      )
      (libsource (lib "easyedapro") (part "0603WAF9093T5E"))
    )
    (comp (ref "R8")
      (value "137kΩ")
      (footprint "easyedapro:R0603")
      (fields
        (field (name "Manufacturer Part") "0603WAF1373T5E")
        (field (name "Manufacturer") "UNI-ROYAL(厚声)")
      )
      (libsource (lib "easyedapro") (part "0603WAF1373T5E"))
    )
    (comp (ref "R9")
      (value "1kΩ")
      (footprint "easyedapro:R0603")
      (fields
        (field (name "Manufacturer Part") "0603WAF1001T5E")
        (field (name "Manufacturer") "UNI-ROYAL(厚声)")
      )
      (libsource (lib "easyedapro") (part "0603WAF1001T5E"))
    )
    (comp (ref "R10")
      (value "1kΩ")
      (footprint "easyedapro:R0603")
      (fields
        (field (name "Manufacturer Part") "0603WAF1001T5E")
        (field (name "Manufacturer") "UNI-ROYAL(厚声)")
      )
      (libsource (lib "easyedapro") (part "0603WAF1001T5E"))
    )
    (comp (ref "R11")
      (value "1kΩ")
      (footprint "easyedapro:R0603")
      (fields
        (field (name "Manufacturer Part") "0603WAF1001T5E")
        (field (name "Manufacturer") "UNI-ROYAL(厚声)")
      )
      (libsource (lib "easyedapro") (part "0603WAF1001T5E"))
    )
    (comp (ref "R12")
      (value "1kΩ")
      (footprint "easyedapro:R0603")
      (fields
        (field (name "Manufacturer Part") "0603WAF1001T5E")
        (field (name "Manufacturer") "UNI-ROYAL(厚声)")
      )
      (libsource (lib "easyedapro") (part "0603WAF1001T5E"))
    )
    (comp (ref "R13")
      (value "1kΩ")
      (footprint "easyedapro:R0603")
      (fields
        (field (name "Manufacturer Part") "0603WAF1001T5E")
        (field (name "Manufacturer") "UNI-ROYAL(厚声)")
      )
      (libsource (lib "easyedapro") (part "0603WAF1001T5E"))
    )
    (comp (ref "R14")
      (value "1kΩ")
      (footprint "easyedapro:R0603")
      (fields
        (field (name "Manufacturer Part") "0603WAF1001T5E")
        (field (name "Manufacturer") "UNI-ROYAL(厚声)")
      )
      (libsource (lib "easyedapro") (part "0603WAF1001T5E"))
    )
    (comp (ref "R15")
      (value "1kΩ")
      (footprint "easyedapro:R0603")
      (fields
        (field (name "Manufacturer Part") "0603WAF1001T5E")
        (field (name "Manufacturer") "UNI-ROYAL(厚声)")
      )
      (libsource (lib "easyedapro") (part "0603WAF1001T5E"))
    )
    (comp (ref "R16")
      (value "1kΩ")
      (footprint "easyedapro:R0603")
      (fields
        (field (name "Manufacturer Part") "0603WAF1001T5E")
        (field (name "Manufacturer") "UNI-ROYAL(厚声)")
      )
      (libsource (lib "easyedapro") (part "0603WAF1001T5E"))
    )
    (comp (ref "R17")
      (value "10kΩ")
      (footprint "easyedapro:R0603")
      (fields
        (field (name "Manufacturer Part") "0603WAF1002T5E")
        (field (name "Manufacturer") "UNI-ROYAL(厚声)")
      )
      (libsource (lib "easyedapro") (part "0603WAF1002T5E"))
    )
    (comp (ref "R18")
      (value "100Ω")
      (footprint "easyedapro:R0402")
      (fields (field (name "Manufacturer Part") "RC0402FR-07100RL") (field (name "Manufacturer") "YAGEO(国巨)"))
      (libsource (lib "easyedapro") (part "RC0402FR-07100RL"))
    )
    (comp (ref "R19")
      (value "5.1kΩ")
      (footprint "easyedapro:R0603")
      (fields
        (field (name "Manufacturer Part") "0603WAF5101T5E")
        (field (name "Manufacturer") "UNI-ROYAL(厚声)")
      )
      (libsource (lib "easyedapro") (part "0603WAF5101T5E"))
    )
    (comp (ref "R20")
      (value "5.1kΩ")
      (footprint "easyedapro:R0603")
      (fields
        (field (name "Manufacturer Part") "0603WAF5101T5E")
        (field (name "Manufacturer") "UNI-ROYAL(厚声)")
      )
      (libsource (lib "easyedapro") (part "0603WAF5101T5E"))
    )
    (comp (ref "R21")
      (value "3.57kΩ")
      (footprint "easyedapro:R0603")
      (fields
        (field (name "Manufacturer Part") "0603WAF3571T5E")
        (field (name "Manufacturer") "UNI-ROYAL(厚声)")
      )
      (libsource (lib "easyedapro") (part "0603WAF3571T5E"))
    )
    (comp (ref "R22")
      (value "7.32kΩ")
      (footprint "easyedapro:R0603")
      (fields
        (field (name "Manufacturer Part") "0603WAF7321T5E")
        (field (name "Manufacturer") "UNI-ROYAL(厚声)")
      )
      (libsource (lib "easyedapro") (part "0603WAF7321T5E"))
    )
    (comp (ref "R23")
      (value "3.57kΩ")
      (footprint "easyedapro:R0603")
      (fields
        (field (name "Manufacturer Part") "0603WAF3571T5E")
        (field (name "Manufacturer") "UNI-ROYAL(厚声)")
      )
      (libsource (lib "easyedapro") (part "0603WAF3571T5E"))
    )
    (comp (ref "R24")
      (value "1.82kΩ")
      (footprint "easyedapro:R0603")
      (fields
        (field (name "Manufacturer Part") "0603WAF1821T5E")
        (field (name "Manufacturer") "UNI-ROYAL(厚声)")
      )
      (libsource (lib "easyedapro") (part "0603WAF1821T5E"))
    )
    (comp (ref "R25")
      (value "11.3kΩ")
      (footprint "easyedapro:R0603")
      (fields
        (field (name "Manufacturer Part") "0603WAF1132T5E")
        (field (name "Manufacturer") "UNI-ROYAL(厚声)")
      )
      (libsource (lib "easyedapro") (part "0603WAF1132T5E"))
    )
    (comp (ref "R26")
      (value "5.49kΩ")
      (footprint "easyedapro:R0603")
      (fields (field (name "Manufacturer Part") "RTT035491FTP") (field (name "Manufacturer") "RALEC(旺诠)"))
      (libsource (lib "easyedapro") (part "RTT035491FTP"))
    )
    (comp (ref "R27")
      (value "909Ω")
      (footprint "easyedapro:R0603")
      (fields (field (name "Manufacturer Part") "RTT039090FTP") (field (name "Manufacturer") "RALEC(旺诠)"))
      (libsource (lib "easyedapro") (part "RTT039090FTP"))
    )
    (comp (ref "R28")
      (value "1.78kΩ")
      (footprint "easyedapro:R0603")
      (fields (field (name "Manufacturer Part") "RTT031781FTP") (field (name "Manufacturer") "RALEC(旺诠)"))
      (libsource (lib "easyedapro") (part "RTT031781FTP"))
    )
    (comp (ref "R29")
      (value "1.37kΩ")
      (footprint "easyedapro:R0603")
      (fields
        (field (name "Manufacturer Part") "0603WAF1371T5E")
        (field (name "Manufacturer") "UNI-ROYAL(厚声)")
      )
      (libsource (lib "easyedapro") (part "0603WAF1371T5E"))
    )
    (comp (ref "R30")
      (value "2.74kΩ")
      (footprint "easyedapro:R0603")
      (fields
        (field (name "Manufacturer Part") "0603WAF2741T5E")
        (field (name "Manufacturer") "UNI-ROYAL(厚声)")
      )
      (libsource (lib "easyedapro") (part "0603WAF2741T5E"))
    )
    (comp (ref "R31")
      (value "7.15kΩ")
      (footprint "easyedapro:R0603")
      (fields
        (field (name "Manufacturer Part") "0603WAF7151T5E")
        (field (name "Manufacturer") "UNI-ROYAL(厚声)")
      )
      (libsource (lib "easyedapro") (part "0603WAF7151T5E"))
    )
    (comp (ref "R32")
      (value "3.57kΩ")
      (footprint "easyedapro:R0603")
      (fields
        (field (name "Manufacturer Part") "0603WAF3571T5E")
        (field (name "Manufacturer") "UNI-ROYAL(厚声)")
      )
      (libsource (lib "easyedapro") (part "0603WAF3571T5E"))
    )
    (comp (ref "R33")
      (value "10kΩ")
      (footprint "easyedapro:R0603")
      (fields
        (field (name "Manufacturer Part") "0603WAF1002T5E")
        (field (name "Manufacturer") "UNI-ROYAL(厚声)")
      )
      (libsource (lib "easyedapro") (part "0603WAF1002T5E"))
    )
    (comp (ref "R34")
      (value "10kΩ")
      (footprint "easyedapro:R0603")
      (fields
        (field (name "Manufacturer Part") "0603WAF1002T5E")
        (field (name "Manufacturer") "UNI-ROYAL(厚声)")
      )
      (libsource (lib "easyedapro") (part "0603WAF1002T5E"))
    )
    (comp (ref "R35")
      (value "6.98kΩ")
      (footprint "easyedapro:R0603")
      (fields
        (field (name "Manufacturer Part") "0603WAF6981T5E")
        (field (name "Manufacturer") "UNI-ROYAL(厚声)")
      )
      (libsource (lib "easyedapro") (part "0603WAF6981T5E"))
    )
    (comp (ref "R36")
      (value "14kΩ")
      (footprint "easyedapro:R0603")
      (fields
        (field (name "Manufacturer Part") "0603WAF1402T5E")
        (field (name "Manufacturer") "UNI-ROYAL(厚声)")
      )
      (libsource (lib "easyedapro") (part "0603WAF1402T5E"))
    )
    (comp (ref "R37")
      (value "3.57kΩ")
      (footprint "easyedapro:R0603")
      (fields
        (field (name "Manufacturer Part") "0603WAF3571T5E")
        (field (name "Manufacturer") "UNI-ROYAL(厚声)")
      )
      (libsource (lib "easyedapro") (part "0603WAF3571T5E"))
    )
    (comp (ref "R38")
      (value "7.32kΩ")
      (footprint "easyedapro:R0603")
      (fields
        (field (name "Manufacturer Part") "0603WAF7321T5E")
        (field (name "Manufacturer") "UNI-ROYAL(厚声)")
      )
      (libsource (lib "easyedapro") (part "0603WAF7321T5E"))
    )
    (comp (ref "R39")
      (value "3.57kΩ")
      (footprint "easyedapro:R0603")
      (fields
        (field (name "Manufacturer Part") "0603WAF3571T5E")
        (field (name "Manufacturer") "UNI-ROYAL(厚声)")
      )
      (libsource (lib "easyedapro") (part "0603WAF3571T5E"))
    )
    (comp (ref "R40")
      (value "1.82kΩ")
      (footprint "easyedapro:R0603")
      (fields
        (field (name "Manufacturer Part") "0603WAF1821T5E")
        (field (name "Manufacturer") "UNI-ROYAL(厚声)")
      )
      (libsource (lib "easyedapro") (part "0603WAF1821T5E"))
    )
    (comp (ref "R41")
      (value "11.3kΩ")
      (footprint "easyedapro:R0603")
      (fields
        (field (name "Manufacturer Part") "0603WAF1132T5E")
        (field (name "Manufacturer") "UNI-ROYAL(厚声)")
      )
      (libsource (lib "easyedapro") (part "0603WAF1132T5E"))
    )
    (comp (ref "R42")
      (value "5.49kΩ")
      (footprint "easyedapro:R0603")
      (fields (field (name "Manufacturer Part") "RTT035491FTP") (field (name "Manufacturer") "RALEC(旺诠)"))
      (libsource (lib "easyedapro") (part "RTT035491FTP"))
    )
    (comp (ref "R43")
      (value "909Ω")
      (footprint "easyedapro:R0603")
      (fields (field (name "Manufacturer Part") "RTT039090FTP") (field (name "Manufacturer") "RALEC(旺诠)"))
      (libsource (lib "easyedapro") (part "RTT039090FTP"))
    )
    (comp (ref "R44")
      (value "1.78kΩ")
      (footprint "easyedapro:R0603")
      (fields (field (name "Manufacturer Part") "RTT031781FTP") (field (name "Manufacturer") "RALEC(旺诠)"))
      (libsource (lib "easyedapro") (part "RTT031781FTP"))
    )
    (comp (ref "R45")
      (value "1.37kΩ")
      (footprint "easyedapro:R0603")
      (fields
        (field (name "Manufacturer Part") "0603WAF1371T5E")
        (field (name "Manufacturer") "UNI-ROYAL(厚声)")
      )
      (libsource (lib "easyedapro") (part "0603WAF1371T5E"))
    )
    (comp (ref "R46")
      (value "2.74kΩ")
      (footprint "easyedapro:R0603")
      (fields
        (field (name "Manufacturer Part") "0603WAF2741T5E")
        (field (name "Manufacturer") "UNI-ROYAL(厚声)")
      )
      (libsource (lib "easyedapro") (part "0603WAF2741T5E"))
    )
    (comp (ref "R47")
      (value "7.15kΩ")
      (footprint "easyedapro:R0603")
      (fields
        (field (name "Manufacturer Part") "0603WAF7151T5E")
        (field (name "Manufacturer") "UNI-ROYAL(厚声)")
      )
      (libsource (lib "easyedapro") (part "0603WAF7151T5E"))
    )
    (comp (ref "R48")
      (value "3.57kΩ")
      (footprint "easyedapro:R0603")
      (fields
        (field (name "Manufacturer Part") "0603WAF3571T5E")
        (field (name "Manufacturer") "UNI-ROYAL(厚声)")
      )
      (libsource (lib "easyedapro") (part "0603WAF3571T5E"))
    )
    (comp (ref "R49")
      (value "10kΩ")
      (footprint "easyedapro:R0603")
      (fields
        (field (name "Manufacturer Part") "0603WAF1002T5E")
        (field (name "Manufacturer") "UNI-ROYAL(厚声)")
      )
      (libsource (lib "easyedapro") (part "0603WAF1002T5E"))
    )
    (comp (ref "R50")
      (value "10kΩ")
      (footprint "easyedapro:R0603")
      (fields
        (field (name "Manufacturer Part") "0603WAF1002T5E")
        (field (name "Manufacturer") "UNI-ROYAL(厚声)")
      )
      (libsource (lib "easyedapro") (part "0603WAF1002T5E"))
    )
    (comp (ref "R51")
      (value "6.98kΩ")
      (footprint "easyedapro:R0603")
      (fields
        (field (name "Manufacturer Part") "0603WAF6981T5E")
        (field (name "Manufacturer") "UNI-ROYAL(厚声)")
      )
      (libsource (lib "easyedapro") (part "0603WAF6981T5E"))
    )
    (comp (ref "R52")
      (value "14kΩ")
      (footprint "easyedapro:R0603")
      (fields
        (field (name "Manufacturer Part") "0603WAF1402T5E")
        (field (name "Manufacturer") "UNI-ROYAL(厚声)")
      )
      (libsource (lib "easyedapro") (part "0603WAF1402T5E"))
    )
    (comp (ref "TP1")
      (value "~")
      (footprint "easyedapro:Test-Point-0.5mm")
      (description "Test Point 测试点")
      (libsource (lib "easyedapro") (part "Test-Point"))
    )
    (comp (ref "TP2")
      (value "~")
      (footprint "easyedapro:Test-Point-0.5mm")
      (description "Test Point 测试点")
      (libsource (lib "easyedapro") (part "Test-Point"))
    )
    (comp (ref "TP3")
      (value "~")
      (footprint "easyedapro:Test-Point-0.5mm")
      (description "Test Point 测试点")
      (libsource (lib "easyedapro") (part "Test-Point"))
    )
    (comp (ref "TP4")
      (value "~")
      (footprint "easyedapro:Test-Point-0.5mm")
      (description "Test Point 测试点")
      (libsource (lib "easyedapro") (part "Test-Point"))
    )
    (comp (ref "U1")
      (value "TPS7A4901DGNR")
      (footprint "easyedapro:HVSSOP-8_L3.0-W3.0-P0.65-LS4.9-BL-EP_DGN0008D")
      (fields (field (name "Manufacturer") "TI(德州仪器)"))
      (libsource (lib "easyedapro") (part "TPS7A4901DGNR"))
    )
    (comp (ref "U2")
      (value "TPS62143RGTR")
      (footprint "easyedapro:TQFN-16_L3.0-W3.0-P0.50-TL-EP1.7")
      (fields (field (name "Manufacturer") "TI(德州仪器)"))
      (libsource (lib "easyedapro") (part "TPS62143RGTR"))
    )
    (comp (ref "U3")
      (value "TPS7A3001DGNR")
      (footprint "easyedapro:HVSSOP-8_L3.0-W3.0-P0.65-LS4.9-BL-EP_DGN0008D")
      (fields (field (name "Manufacturer") "TI(德州仪器)"))
      (libsource (lib "easyedapro") (part "TPS7A3001DGNR"))
    )
    (comp (ref "U4")
      (value "LP5907MFX-3.3/NOPB")
      (footprint "easyedapro:SOT-23-5_L3.0-W1.7-P0.95-LS2.8-BR")
      (fields (field (name "Manufacturer") "TI(德州仪器)"))
      (libsource (lib "easyedapro") (part "LP5907MFX-3.3/NOPB"))
    )
    (comp (ref "U5")
      (value "NCV7240BDPR2G")
      (footprint "easyedapro:SSOP-24_L8.7-W3.9-P0.65-LS6.0-BL")
      (fields (field (name "Manufacturer") "onsemi(安森美)"))
      (libsource (lib "easyedapro") (part "NCV7240BDPR2G"))
    )
    (comp (ref "U6")
      (value "STM32F070F6P6")
      (footprint "easyedapro:TSSOP-20_L6.5-W4.4-P0.65-LS6.4-BL")
      (fields (field (name "Manufacturer") "ST(意法半导体)"))
      (libsource (lib "easyedapro") (part "STM32F070F6P6"))
    )
    (comp (ref "U7")
      (value "OPA4187IDR")
      (footprint "easyedapro:SOIC-14_L8.7-W3.9-P1.27-LS6.0-BL")
      (fields (field (name "Manufacturer") "TI(德州仪器)"))
      (libsource (lib "easyedapro") (part "OPA4187IDR"))
    )
    (comp (ref "U8")
      (value "OPA4187IDR")
      (footprint "easyedapro:SOIC-14_L8.7-W3.9-P1.27-LS6.0-BL")
      (fields (field (name "Manufacturer") "TI(德州仪器)"))
      (libsource (lib "easyedapro") (part "OPA4187IDR"))
    )
    (comp (ref "U9")
      (value "OPA4187IDR")
      (footprint "easyedapro:SOIC-14_L8.7-W3.9-P1.27-LS6.0-BL")
      (fields (field (name "Manufacturer") "TI(德州仪器)"))
      (libsource (lib "easyedapro") (part "OPA4187IDR"))
    )
    (comp (ref "U10")
      (value "OPA4187IDR")
      (footprint "easyedapro:SOIC-14_L8.7-W3.9-P1.27-LS6.0-BL")
      (fields (field (name "Manufacturer") "TI(德州仪器)"))
      (libsource (lib "easyedapro") (part "OPA4187IDR"))
    )
    (comp (ref "USB1")
      (value "TYPE-C16PIN")
      (footprint "easyedapro:USB-C-SMD_TYPE-C16PIN")
      (fields (field (name "Manufacturer") "SHOU HAN(首韩)"))
      (libsource (lib "easyedapro") (part "TYPE-C16PIN"))
    )
    (comp (ref "X1")
      (value "8MHz")
      (footprint "easyedapro:CRYSTAL-SMD_4P-L3.2-W2.5-BL")
      (fields
        (field (name "Manufacturer Part") "3225 8M 12PF 10PPM")
        (field (name "Manufacturer") "SOSET(索斯特)")
      )
      (libsource (lib "easyedapro") (part "3225 8M 12PF 10PPM"))
    )
    (comp (ref "C55")
      (value "10uF")
      (footprint "easyedapro:C0805")
      (description "Capacitance:10uF Tolerance:±10% Tolerance:±10% Voltage Rating:25V Temperature Coefficient:X5R")
      (fields
        (field (name "Manufacturer Part") "CL21A106KAYNNNE")
        (field (name "Manufacturer") "SAMSUNG(三星)")
      )
      (libsource (lib "easyedapro") (part "CL21A106KAYNNNE"))
    )
    (comp (ref "C56")
      (value "100nF")
      (footprint "easyedapro:C0603")
      (fields
        (field (name "Manufacturer Part") "CC0603KRX7R9BB104")
        (field (name "Manufacturer") "YAGEO(国巨)")
      )
      (libsource (lib "easyedapro") (part "CC0603KRX7R9BB104"))
    )
    (comp (ref "C57")
      (value "10uF")
      (footprint "easyedapro:C0805")
      (description "Capacitance:10uF Tolerance:±10% Tolerance:±10% Voltage Rating:25V Temperature Coefficient:X5R")
      (fields
        (field (name "Manufacturer Part") "CL21A106KAYNNNE")
        (field (name "Manufacturer") "SAMSUNG(三星)")
      )
      (libsource (lib "easyedapro") (part "CL21A106KAYNNNE"))
    )
    (comp (ref "C58")
      (value "100nF")
      (footprint "easyedapro:C0603")
      (fields
        (field (name "Manufacturer Part") "CC0603KRX7R9BB104")
        (field (name "Manufacturer") "YAGEO(国巨)")
      )
      (libsource (lib "easyedapro") (part "CC0603KRX7R9BB104"))
    )
    (comp (ref "CN5")
      (value "BH254V-20P")
      (footprint "easyedapro:CONN-TH_20P-P2.54_0702462001")
      (fields (field (name "Manufacturer") "XFCN(兴飞)"))
      (libsource (lib "easyedapro") (part "BH254V-20P"))
    )
    (comp (ref "CN6")
      (value "X2510WV-02-N0SN")
      (footprint "easyedapro:CONN-TH_2P-X2510WV-02-N0SN")
      (fields (field (name "Manufacturer") "XKB Connection(中国星坤)"))
      (libsource (lib "easyedapro") (part "X2510WV-02-N0SN"))
    )
    (comp (ref "K9")
      (value "G6K-2F-Y-TR DC5")
      (footprint "easyedapro:RELAY-SMD_G6K-2F-X-XX")
      (fields (field (name "Manufacturer") "OMRON(欧姆龙)"))
      (libsource (lib "easyedapro") (part "G6K-2F-Y-DC5"))
    )
    (comp (ref "K10")
      (value "G6K-2F-Y-TR DC5")
      (footprint "easyedapro:RELAY-SMD_G6K-2F-X-XX")
      (fields (field (name "Manufacturer") "OMRON(欧姆龙)"))
      (libsource (lib "easyedapro") (part "G6K-2F-Y-DC5"))
    )
    (comp (ref "K11")
      (value "G6K-2F-Y-TR DC5")
      (footprint "easyedapro:RELAY-SMD_G6K-2F-X-XX")
      (fields (field (name "Manufacturer") "OMRON(欧姆龙)"))
      (libsource (lib "easyedapro") (part "G6K-2F-Y-DC5"))
    )
    (comp (ref "K12")
      (value "G6K-2F-Y-TR DC5")
      (footprint "easyedapro:RELAY-SMD_G6K-2F-X-XX")
      (fields (field (name "Manufacturer") "OMRON(欧姆龙)"))
      (libsource (lib "easyedapro") (part "G6K-2F-Y-DC5"))
    )
    (comp (ref "K13")
      (value "G6K-2F-Y-TR DC5")
      (footprint "easyedapro:RELAY-SMD_G6K-2F-X-XX")
      (fields (field (name "Manufacturer") "OMRON(欧姆龙)"))
      (libsource (lib "easyedapro") (part "G6K-2F-Y-DC5"))
    )
    (comp (ref "LED13")
      (value "A-SP192DGHC-C01-4T")
      (footprint "easyedapro:LED0603-FD")
      (fields (field (name "Manufacturer") "Amicc(欧密格光电)"))
      (libsource (lib "easyedapro") (part "A-SP192DGHC-C01-4T"))
    )
    (comp (ref "LED14")
      (value "A-SP192DGHC-C01-4T")
      (footprint "easyedapro:LED0603-FD")
      (fields (field (name "Manufacturer") "Amicc(欧密格光电)"))
      (libsource (lib "easyedapro") (part "A-SP192DGHC-C01-4T"))
    )
    (comp (ref "LED15")
      (value "A-SP192DGHC-C01-4T")
      (footprint "easyedapro:LED0603-FD")
      (fields (field (name "Manufacturer") "Amicc(欧密格光电)"))
      (libsource (lib "easyedapro") (part "A-SP192DGHC-C01-4T"))
    )
    (comp (ref "LED16")
      (value "A-SP192DGHC-C01-4T")
      (footprint "easyedapro:LED0603-FD")
      (fields (field (name "Manufacturer") "Amicc(欧密格光电)"))
      (libsource (lib "easyedapro") (part "A-SP192DGHC-C01-4T"))
    )
    (comp (ref "LED17")
      (value "A-SP192DGHC-C01-4T")
      (footprint "easyedapro:LED0603-FD")
      (fields (field (name "Manufacturer") "Amicc(欧密格光电)"))
      (libsource (lib "easyedapro") (part "A-SP192DGHC-C01-4T"))
    )
    (comp (ref "R53")
      (value "40kΩ")
      (footprint "easyedapro:R0603")
      (fields (field (name "Manufacturer Part") "SCR0603F40K") (field (name "Manufacturer") "VO(翔胜)"))
      (libsource (lib "easyedapro") (part "SCR0603F40K"))
    )
    (comp (ref "R54")
      (value "40kΩ")
      (footprint "easyedapro:R0603")
      (fields (field (name "Manufacturer Part") "SCR0603F40K") (field (name "Manufacturer") "VO(翔胜)"))
      (libsource (lib "easyedapro") (part "SCR0603F40K"))
    )
    (comp (ref "R55")
      (value "10kΩ")
      (footprint "easyedapro:R0603")
      (fields
        (field (name "Manufacturer Part") "0603WAF1002T5E")
        (field (name "Manufacturer") "UNI-ROYAL(厚声)")
      )
      (libsource (lib "easyedapro") (part "0603WAF1002T5E"))
    )
    (comp (ref "R56")
      (value "10kΩ")
      (footprint "easyedapro:R0603")
      (fields
        (field (name "Manufacturer Part") "0603WAF1002T5E")
        (field (name "Manufacturer") "UNI-ROYAL(厚声)")
      )
      (libsource (lib "easyedapro") (part "0603WAF1002T5E"))
    )
    (comp (ref "R57")
      (value "40kΩ")
      (footprint "easyedapro:R0603")
      (fields (field (name "Manufacturer Part") "SCR0603F40K") (field (name "Manufacturer") "VO(翔胜)"))
      (libsource (lib "easyedapro") (part "SCR0603F40K"))
    )
    (comp (ref "R58")
      (value "40kΩ")
      (footprint "easyedapro:R0603")
      (fields (field (name "Manufacturer Part") "SCR0603F40K") (field (name "Manufacturer") "VO(翔胜)"))
      (libsource (lib "easyedapro") (part "SCR0603F40K"))
    )
    (comp (ref "R59")
      (value "10kΩ")
      (footprint "easyedapro:R0603")
      (fields
        (field (name "Manufacturer Part") "0603WAF1002T5E")
        (field (name "Manufacturer") "UNI-ROYAL(厚声)")
      )
      (libsource (lib "easyedapro") (part "0603WAF1002T5E"))
    )
    (comp (ref "R60")
      (value "10kΩ")
      (footprint "easyedapro:R0603")
      (fields
        (field (name "Manufacturer Part") "0603WAF1002T5E")
        (field (name "Manufacturer") "UNI-ROYAL(厚声)")
      )
      (libsource (lib "easyedapro") (part "0603WAF1002T5E"))
    )
    (comp (ref "R61")
      (value "1kΩ")
      (footprint "easyedapro:R0603")
      (fields
        (field (name "Manufacturer Part") "0603WAF1001T5E")
        (field (name "Manufacturer") "UNI-ROYAL(厚声)")
      )
      (libsource (lib "easyedapro") (part "0603WAF1001T5E"))
    )
    (comp (ref "R62")
      (value "1kΩ")
      (footprint "easyedapro:R0603")
      (fields
        (field (name "Manufacturer Part") "0603WAF1001T5E")
        (field (name "Manufacturer") "UNI-ROYAL(厚声)")
      )
      (libsource (lib "easyedapro") (part "0603WAF1001T5E"))
    )
    (comp (ref "R63")
      (value "1kΩ")
      (footprint "easyedapro:R0603")
      (fields
        (field (name "Manufacturer Part") "0603WAF1001T5E")
        (field (name "Manufacturer") "UNI-ROYAL(厚声)")
      )
      (libsource (lib "easyedapro") (part "0603WAF1001T5E"))
    )
    (comp (ref "R64")
      (value "1kΩ")
      (footprint "easyedapro:R0603")
      (fields
        (field (name "Manufacturer Part") "0603WAF1001T5E")
        (field (name "Manufacturer") "UNI-ROYAL(厚声)")
      )
      (libsource (lib "easyedapro") (part "0603WAF1001T5E"))
    )
    (comp (ref "R65")
      (value "1kΩ")
      (footprint "easyedapro:R0603")
      (fields
        (field (name "Manufacturer Part") "0603WAF1001T5E")
        (field (name "Manufacturer") "UNI-ROYAL(厚声)")
      )
      (libsource (lib "easyedapro") (part "0603WAF1001T5E"))
    )
    (comp (ref "R66")
      (value "100kΩ")
      (footprint "easyedapro:R0603")
      (fields (field (name "Manufacturer Part") "RC0603FR-07100KL") (field (name "Manufacturer") "YAGEO(国巨)"))
      (libsource (lib "easyedapro") (part "RC0603FR-07100KL"))
    )
    (comp (ref "R67")
      (value "100kΩ")
      (footprint "easyedapro:R0603")
      (fields (field (name "Manufacturer Part") "RC0603FR-07100KL") (field (name "Manufacturer") "YAGEO(国巨)"))
      (libsource (lib "easyedapro") (part "RC0603FR-07100KL"))
    )
    (comp (ref "R68")
      (value "1kΩ")
      (footprint "easyedapro:R0603")
      (fields
        (field (name "Manufacturer Part") "0603WAF1001T5E")
        (field (name "Manufacturer") "UNI-ROYAL(厚声)")
      )
      (libsource (lib "easyedapro") (part "0603WAF1001T5E"))
    )
    (comp (ref "R69")
      (value "1kΩ")
      (footprint "easyedapro:R0603")
      (fields
        (field (name "Manufacturer Part") "0603WAF1001T5E")
        (field (name "Manufacturer") "UNI-ROYAL(厚声)")
      )
      (libsource (lib "easyedapro") (part "0603WAF1001T5E"))
    )
    (comp (ref "R70")
      (value "100kΩ")
      (footprint "easyedapro:R0603")
      (fields (field (name "Manufacturer Part") "RC0603FR-07100KL") (field (name "Manufacturer") "YAGEO(国巨)"))
      (libsource (lib "easyedapro") (part "RC0603FR-07100KL"))
    )
    (comp (ref "R71")
      (value "100kΩ")
      (footprint "easyedapro:R0603")
      (fields (field (name "Manufacturer Part") "RC0603FR-07100KL") (field (name "Manufacturer") "YAGEO(国巨)"))
      (libsource (lib "easyedapro") (part "RC0603FR-07100KL"))
    )
    (comp (ref "R72")
      (value "1kΩ")
      (footprint "easyedapro:R0603")
      (fields
        (field (name "Manufacturer Part") "0603WAF1001T5E")
        (field (name "Manufacturer") "UNI-ROYAL(厚声)")
      )
      (libsource (lib "easyedapro") (part "0603WAF1001T5E"))
    )
    (comp (ref "R73")
      (value "1kΩ")
      (footprint "easyedapro:R0603")
      (fields
        (field (name "Manufacturer Part") "0603WAF1001T5E")
        (field (name "Manufacturer") "UNI-ROYAL(厚声)")
      )
      (libsource (lib "easyedapro") (part "0603WAF1001T5E"))
    )
    (comp (ref "R74")
      (value "1.65MΩ")
      (footprint "easyedapro:R0603")
      (fields (field (name "Manufacturer Part") "RTT031654FTP") (field (name "Manufacturer") "RALEC(旺诠)"))
      (libsource (lib "easyedapro") (part "RTT031654FTP"))
    )
    (comp (ref "R75")
      (value "1kΩ")
      (footprint "easyedapro:R0603")
      (fields
        (field (name "Manufacturer Part") "0603WAF1001T5E")
        (field (name "Manufacturer") "UNI-ROYAL(厚声)")
      )
      (libsource (lib "easyedapro") (part "0603WAF1001T5E"))
    )
    (comp (ref "SW1")
      (value "DSWB01LHGET")
      (footprint "easyedapro:SW-TH_DSWB01LHGETR")
      (fields (field (name "Manufacturer") "HanElectricity(瀚源)"))
      (libsource (lib "easyedapro") (part "DSWB01LHGET_C25503176"))
    )
    (comp (ref "SW2")
      (value "DSWB02LHGET")
      (footprint "easyedapro:SW-TH_DSWB02LHGET")
      (description "Type:平拨,凸起式 Circuit:SPST Number of Positions:2Bit Lead Pitch:2.54mm Operating Life:- Color:Red")
      (fields (field (name "Manufacturer") "YE"))
      (libsource (lib "easyedapro") (part "DSWB02LHGET"))
    )
    (comp (ref "U11")
      (value "OPA4187IDR")
      (footprint "easyedapro:SOIC-14_L8.7-W3.9-P1.27-LS6.0-BL")
      (fields (field (name "Manufacturer") "TI(德州仪器)"))
      (libsource (lib "easyedapro") (part "OPA4187IDR"))
    )
    (comp (ref "U12")
      (value "NCV7240BDPR2G")
      (footprint "easyedapro:SSOP-24_L8.7-W3.9-P0.65-LS6.0-BL")
      (fields (field (name "Manufacturer") "onsemi(安森美)"))
      (libsource (lib "easyedapro") (part "NCV7240BDPR2G"))
    )
    (comp (ref "U13")
      (value "OPA4187IDR")
      (footprint "easyedapro:SOIC-14_L8.7-W3.9-P1.27-LS6.0-BL")
      (fields (field (name "Manufacturer") "TI(德州仪器)"))
      (libsource (lib "easyedapro") (part "OPA4187IDR"))
    )
    (comp (ref "U14")
      (value "PZ127-2-18-Z")
      (footprint "easyedapro:HDR-TH_36P-P1.27-V-M-R2-C18-S1.27")
      (fields (field (name "Manufacturer") "HCTL(华灿天禄)"))
      (libsource (lib "easyedapro") (part "PZ127-2-18-Z"))
    )
  )
  (nets
    (net (code "1") (name "+9V") (class "Default")
      (node (ref "C19") (pin "2") (pinfunction "2_2") (pintype "unspecified"))
      (node (ref "C20") (pin "2") (pinfunction "2_2") (pintype "input"))
      (node (ref "C29") (pin "2") (pinfunction "2_2") (pintype "unspecified"))
      (node (ref "C30") (pin "2") (pinfunction "2_2") (pintype "input"))
      (node (ref "C37") (pin "2") (pinfunction "2_2") (pintype "unspecified"))
      (node (ref "C38") (pin "2") (pinfunction "2_2") (pintype "input"))
      (node (ref "C47") (pin "2") (pinfunction "2_2") (pintype "unspecified"))
      (node (ref "C48") (pin "2") (pinfunction "2_2") (pintype "input"))
      (node (ref "C5") (pin "2") (pinfunction "2_2") (pintype "input"))
      (node (ref "C55") (pin "2") (pinfunction "2_2") (pintype "unspecified"))
      (node (ref "C56") (pin "2") (pinfunction "2_2") (pintype "input"))
      (node (ref "C57") (pin "2") (pinfunction "2_2") (pintype "unspecified"))
      (node (ref "C58") (pin "2") (pinfunction "2_2") (pintype "input"))
      (node (ref "C7") (pin "2") (pinfunction "2_2") (pintype "input"))
      (node (ref "LED3") (pin "2") (pinfunction "A_2") (pintype "unspecified"))
      (node (ref "R1") (pin "2") (pinfunction "2_2") (pintype "input"))
      (node (ref "TP1") (pin "1") (pinfunction "1_1") (pintype "unspecified"))
      (node (ref "U1") (pin "1") (pinfunction "OUT_1") (pintype "unspecified"))
      (node (ref "U10") (pin "4") (pinfunction "V+_4") (pintype "unspecified"))
      (node (ref "U11") (pin "4") (pinfunction "V+_4") (pintype "unspecified"))
      (node (ref "U13") (pin "4") (pinfunction "V+_4") (pintype "unspecified"))
      (node (ref "U7") (pin "4") (pinfunction "V+_4") (pintype "unspecified"))
      (node (ref "U8") (pin "4") (pinfunction "V+_4") (pintype "unspecified"))
      (node (ref "U9") (pin "4") (pinfunction "V+_4") (pintype "unspecified"))
    )
    (net (code "2") (name "+12V") (class "Default")
      (node (ref "C1") (pin "1") (pinfunction "1_1") (pintype "input"))
      (node (ref "C2") (pin "2") (pinfunction "2_2") (pintype "input"))
      (node (ref "C4") (pin "2") (pinfunction "2_2") (pintype "input"))
      (node (ref "CN1") (pin "1") (pinfunction "1_1") (pintype "unspecified"))
      (node (ref "U1") (pin "5") (pinfunction "EN_5") (pintype "unspecified"))
      (node (ref "U1") (pin "8") (pinfunction "IN_8") (pintype "unspecified"))
      (node (ref "U2") (pin "10") (pinfunction "AVIN_10") (pintype "unspecified"))
      (node (ref "U2") (pin "11") (pinfunction "PVIN_11") (pintype "unspecified"))
      (node (ref "U2") (pin "12") (pinfunction "PVIN_12") (pintype "unspecified"))
      (node (ref "U2") (pin "13") (pinfunction "EN_13") (pintype "unspecified"))
    )
    (net (code "3") (name "-9V") (class "Default")
      (node (ref "C11") (pin "2") (pinfunction "2_2") (pintype "input"))
      (node (ref "C12") (pin "2") (pinfunction "2_2") (pintype "input"))
      (node (ref "C19") (pin "1") (pinfunction "1_1") (pintype "unspecified"))
      (node (ref "C20") (pin "1") (pinfunction "1_1") (pintype "input"))
      (node (ref "C29") (pin "1") (pinfunction "1_1") (pintype "unspecified"))
      (node (ref "C30") (pin "1") (pinfunction "1_1") (pintype "input"))
      (node (ref "C37") (pin "1") (pinfunction "1_1") (pintype "unspecified"))
      (node (ref "C38") (pin "1") (pinfunction "1_1") (pintype "input"))
      (node (ref "C47") (pin "1") (pinfunction "1_1") (pintype "unspecified"))
      (node (ref "C48") (pin "1") (pinfunction "1_1") (pintype "input"))
      (node (ref "C55") (pin "1") (pinfunction "1_1") (pintype "unspecified"))
      (node (ref "C56") (pin "1") (pinfunction "1_1") (pintype "input"))
      (node (ref "C57") (pin "1") (pinfunction "1_1") (pintype "unspecified"))
      (node (ref "C58") (pin "1") (pinfunction "1_1") (pintype "input"))
      (node (ref "LED4") (pin "1") (pinfunction "K_1") (pintype "unspecified"))
      (node (ref "R7") (pin "2") (pinfunction "2_2") (pintype "input"))
      (node (ref "TP3") (pin "1") (pinfunction "1_1") (pintype "unspecified"))
      (node (ref "U10") (pin "11") (pinfunction "V-_11") (pintype "unspecified"))
      (node (ref "U11") (pin "11") (pinfunction "V-_11") (pintype "unspecified"))
      (node (ref "U13") (pin "11") (pinfunction "V-_11") (pintype "unspecified"))
      (node (ref "U3") (pin "1") (pinfunction "OUT_1") (pintype "unspecified"))
      (node (ref "U7") (pin "11") (pinfunction "V-_11") (pintype "unspecified"))
      (node (ref "U8") (pin "11") (pinfunction "V-_11") (pintype "unspecified"))
      (node (ref "U9") (pin "11") (pinfunction "V-_11") (pintype "unspecified"))
    )
    (net (code "4") (name "-12V") (class "Default")
      (node (ref "C10") (pin "2") (pinfunction "2_2") (pintype "input"))
      (node (ref "CN1") (pin "3") (pinfunction "3_3") (pintype "unspecified"))
      (node (ref "U3") (pin "5") (pinfunction "EN_5") (pintype "unspecified"))
      (node (ref "U3") (pin "8") (pinfunction "IN_8") (pintype "unspecified"))
    )
    (net (code "5") (name "3V3") (class "Default")
      (node (ref "C14") (pin "1") (pinfunction "1_1") (pintype "input"))
      (node (ref "C16") (pin "1") (pinfunction "1_1") (pintype "input"))
      (node (ref "C17") (pin "2") (pinfunction "2_2") (pintype "input"))
      (node (ref "C18") (pin "2") (pinfunction "2_2") (pintype "input"))
      (node (ref "CN2") (pin "3") (pinfunction "3_3") (pintype "unspecified"))
      (node (ref "LED2") (pin "2") (pinfunction "A_2") (pintype "unspecified"))
      (node (ref "TP4") (pin "1") (pinfunction "1_1") (pintype "unspecified"))
      (node (ref "U12") (pin "13") (pinfunction "VDD_13") (pintype "unspecified"))
      (node (ref "U4") (pin "5") (pinfunction "OUT_5") (pintype "unspecified"))
      (node (ref "U5") (pin "13") (pinfunction "VDD_13") (pintype "unspecified"))
      (node (ref "U6") (pin "16") (pinfunction "VDD_16") (pintype "unspecified"))
      (node (ref "U6") (pin "5") (pinfunction "VDDA_5") (pintype "unspecified"))
    )
    (net (code "6") (name "5V") (class "Default")
      (node (ref "C13") (pin "1") (pinfunction "1_1") (pintype "input"))
      (node (ref "C3") (pin "2") (pinfunction "2_2") (pintype "unspecified"))
      (node (ref "C6") (pin "2") (pinfunction "2_2") (pintype "input"))
      (node (ref "K1") (pin "1") (pinfunction "1_1") (pintype "input"))
      (node (ref "K10") (pin "1") (pinfunction "1_1") (pintype "input"))
      (node (ref "K11") (pin "1") (pinfunction "1_1") (pintype "input"))
      (node (ref "K12") (pin "1") (pinfunction "1_1") (pintype "input"))
      (node (ref "K13") (pin "1") (pinfunction "1_1") (pintype "input"))
      (node (ref "K2") (pin "1") (pinfunction "1_1") (pintype "input"))
      (node (ref "K3") (pin "1") (pinfunction "1_1") (pintype "input"))
      (node (ref "K4") (pin "1") (pinfunction "1_1") (pintype "input"))
      (node (ref "K5") (pin "1") (pinfunction "1_1") (pintype "input"))
      (node (ref "K6") (pin "1") (pinfunction "1_1") (pintype "input"))
      (node (ref "K7") (pin "1") (pinfunction "1_1") (pintype "input"))
      (node (ref "K8") (pin "1") (pinfunction "1_1") (pintype "input"))
      (node (ref "K9") (pin "1") (pinfunction "1_1") (pintype "input"))
      (node (ref "L1") (pin "2") (pinfunction "2_2") (pintype "unspecified"))
      (node (ref "LED1") (pin "2") (pinfunction "A_2") (pintype "unspecified"))
      (node (ref "R10") (pin "2") (pinfunction "2_2") (pintype "input"))
      (node (ref "R11") (pin "2") (pinfunction "2_2") (pintype "input"))
      (node (ref "R12") (pin "2") (pinfunction "2_2") (pintype "input"))
      (node (ref "R13") (pin "2") (pinfunction "2_2") (pintype "input"))
      (node (ref "R14") (pin "2") (pinfunction "2_2") (pintype "input"))
      (node (ref "R15") (pin "2") (pinfunction "2_2") (pintype "input"))
      (node (ref "R16") (pin "2") (pinfunction "2_2") (pintype "input"))
      (node (ref "R61") (pin "2") (pinfunction "2_2") (pintype "input"))
      (node (ref "R62") (pin "2") (pinfunction "2_2") (pintype "input"))
      (node (ref "R63") (pin "2") (pinfunction "2_2") (pintype "input"))
      (node (ref "R64") (pin "2") (pinfunction "2_2") (pintype "input"))
      (node (ref "R65") (pin "2") (pinfunction "2_2") (pintype "input"))
      (node (ref "R9") (pin "2") (pinfunction "2_2") (pintype "input"))
      (node (ref "TP2") (pin "1") (pinfunction "1_1") (pintype "unspecified"))
      (node (ref "U12") (pin "24") (pinfunction "VDDA_24") (pintype "unspecified"))
      (node (ref "U2") (pin "14") (pinfunction "VOS_14") (pintype "unspecified"))
      (node (ref "U4") (pin "1") (pinfunction "IN_1") (pintype "unspecified"))
      (node (ref "U4") (pin "3") (pinfunction "EN_3") (pintype "unspecified"))
      (node (ref "U5") (pin "24") (pinfunction "VDDA_24") (pintype "unspecified"))
    )
    (net (code "7") (name "A1") (class "Default")
      (node (ref "K11") (pin "4") (pinfunction "4_4") (pintype "input"))
      (node (ref "K12") (pin "4") (pinfunction "4_4") (pintype "input"))
      (node (ref "K9") (pin "3") (pinfunction "3_3") (pintype "input"))
      (node (ref "R66") (pin "2") (pinfunction "2_2") (pintype "input"))
    )
    (net (code "8") (name "A1_D") (class "Default")
      (node (ref "K9") (pin "4") (pinfunction "4_4") (pintype "input"))
      (node (ref "U11") (pin "1") (pinfunction "OUTA_1") (pintype "unspecified"))
      (node (ref "U11") (pin "2") (pinfunction "-INA_2") (pintype "unspecified"))
    )
    (net (code "9") (name "A2") (class "Default")
      (node (ref "K10") (pin "3") (pinfunction "3_3") (pintype "input"))
      (node (ref "K13") (pin "4") (pinfunction "4_4") (pintype "input"))
      (node (ref "R70") (pin "2") (pinfunction "2_2") (pintype "input"))
    )
    (net (code "10") (name "A2_D") (class "Default")
      (node (ref "K10") (pin "4") (pinfunction "4_4") (pintype "input"))
      (node (ref "U11") (pin "13") (pinfunction "-IND_13") (pintype "unspecified"))
      (node (ref "U11") (pin "14") (pinfunction "OUTD_14") (pintype "unspecified"))
    )
    (net (code "11") (name "AMP_CH1") (class "Default")
      (node (ref "K11") (pin "7") (pinfunction "7_7") (pintype "input"))
      (node (ref "U14") (pin "3") (pinfunction "3_3") (pintype "unspecified"))
    )
    (net (code "12") (name "AMP_CH4") (class "Default")
      (node (ref "K13") (pin "7") (pinfunction "7_7") (pintype "input"))
      (node (ref "U14") (pin "6") (pinfunction "6_6") (pintype "unspecified"))
    )
    (net (code "13") (name "AMP_CH8") (class "Default")
      (node (ref "K13") (pin "2") (pinfunction "2_2") (pintype "input"))
      (node (ref "U14") (pin "10") (pinfunction "10_10") (pintype "unspecified"))
    )
    (net (code "14") (name "AMP_CH9") (class "Default")
      (node (ref "K12") (pin "7") (pinfunction "7_7") (pintype "input"))
      (node (ref "U14") (pin "11") (pinfunction "11_11") (pintype "unspecified"))
    )
    (net (code "15") (name "AMP_CH13") (class "Default")
      (node (ref "K12") (pin "2") (pinfunction "2_2") (pintype "input"))
      (node (ref "U14") (pin "15") (pinfunction "15_15") (pintype "unspecified"))
    )
    (net (code "16") (name "AMP_CH16") (class "Default")
      (node (ref "K11") (pin "2") (pinfunction "2_2") (pintype "input"))
      (node (ref "U14") (pin "18") (pinfunction "18_18") (pintype "unspecified"))
    )
    (net (code "17") (name "AMP_CH17") (class "Default")
      (node (ref "U13") (pin "1") (pinfunction "OUTA_1") (pintype "unspecified"))
      (node (ref "U13") (pin "2") (pinfunction "-INA_2") (pintype "unspecified"))
      (node (ref "U14") (pin "19") (pinfunction "19_19") (pintype "unspecified"))
    )
    (net (code "18") (name "AMP_CH18") (class "Default")
      (node (ref "U13") (pin "13") (pinfunction "-IND_13") (pintype "unspecified"))
      (node (ref "U13") (pin "14") (pinfunction "OUTD_14") (pintype "unspecified"))
      (node (ref "U14") (pin "20") (pinfunction "20_20") (pintype "unspecified"))
    )
    (net (code "19") (name "AMP_CH19") (class "Default")
      (node (ref "U13") (pin "6") (pinfunction "-INB_6") (pintype "unspecified"))
      (node (ref "U13") (pin "7") (pinfunction "OUTB_7") (pintype "unspecified"))
      (node (ref "U14") (pin "21") (pinfunction "21_21") (pintype "unspecified"))
    )
    (net (code "20") (name "AMP_CH20") (class "Default")
      (node (ref "U13") (pin "8") (pinfunction "OUTC_8") (pintype "unspecified"))
      (node (ref "U13") (pin "9") (pinfunction "-INC_9") (pintype "unspecified"))
      (node (ref "U14") (pin "22") (pinfunction "22_22") (pintype "unspecified"))
    )
    (net (code "21") (name "AMP_CH22") (class "Default")
      (node (ref "R74") (pin "1") (pinfunction "1_1") (pintype "input"))
      (node (ref "R75") (pin "2") (pinfunction "2_2") (pintype "input"))
      (node (ref "U14") (pin "24") (pinfunction "24_24") (pintype "unspecified"))
    )
    (net (code "22") (name "C1") (class "Default")
      (node (ref "K11") (pin "5") (pinfunction "5_5") (pintype "input"))
      (node (ref "K12") (pin "5") (pinfunction "5_5") (pintype "input"))
      (node (ref "K9") (pin "6") (pinfunction "6_6") (pintype "input"))
      (node (ref "R67") (pin "2") (pinfunction "2_2") (pintype "input"))
    )
    (net (code "23") (name "C1_D") (class "Default")
      (node (ref "K9") (pin "5") (pinfunction "5_5") (pintype "input"))
      (node (ref "U11") (pin "6") (pinfunction "-INB_6") (pintype "unspecified"))
      (node (ref "U11") (pin "7") (pinfunction "OUTB_7") (pintype "unspecified"))
    )
    (net (code "24") (name "C2") (class "Default")
      (node (ref "K10") (pin "6") (pinfunction "6_6") (pintype "input"))
      (node (ref "K13") (pin "5") (pinfunction "5_5") (pintype "input"))
      (node (ref "R71") (pin "2") (pinfunction "2_2") (pintype "input"))
    )
    (net (code "25") (name "C2_D") (class "Default")
      (node (ref "K10") (pin "5") (pinfunction "5_5") (pintype "input"))
      (node (ref "U11") (pin "8") (pinfunction "OUTC_8") (pintype "unspecified"))
      (node (ref "U11") (pin "9") (pinfunction "-INC_9") (pintype "unspecified"))
    )
    (net (code "26") (name "CH1_2HZ_A") (class "Default")
      (node (ref "C21") (pin "2") (pinfunction "2_2") (pintype "unspecified"))
      (node (ref "K7") (pin "3") (pinfunction "3_3") (pintype "input"))
      (node (ref "U7") (pin "6") (pinfunction "-INB_6") (pintype "unspecified"))
      (node (ref "U7") (pin "7") (pinfunction "OUTB_7") (pintype "unspecified"))
    )
    (net (code "27") (name "CH1_8HZ_A") (class "Default")
      (node (ref "C25") (pin "2") (pinfunction "2_2") (pintype "unspecified"))
      (node (ref "K6") (pin "3") (pinfunction "3_3") (pintype "input"))
      (node (ref "U7") (pin "1") (pinfunction "OUTA_1") (pintype "unspecified"))
      (node (ref "U7") (pin "2") (pinfunction "-INA_2") (pintype "unspecified"))
    )
    (net (code "28") (name "CH1_40HZ_A") (class "Default")
      (node (ref "C22") (pin "1") (pinfunction "1_1") (pintype "unspecified"))
      (node (ref "K5") (pin "3") (pinfunction "3_3") (pintype "input"))
      (node (ref "U7") (pin "8") (pinfunction "OUTC_8") (pintype "unspecified"))
      (node (ref "U7") (pin "9") (pinfunction "-INC_9") (pintype "unspecified"))
    )
    (net (code "29") (name "CH1_130HZ_A") (class "Default")
      (node (ref "C28") (pin "1") (pinfunction "1_1") (pintype "input"))
      (node (ref "K4") (pin "3") (pinfunction "3_3") (pintype "input"))
      (node (ref "U7") (pin "13") (pinfunction "-IND_13") (pintype "unspecified"))
      (node (ref "U7") (pin "14") (pinfunction "OUTD_14") (pintype "unspecified"))
    )
    (net (code "30") (name "CH1_530HZ_A") (class "Default")
      (node (ref "C31") (pin "2") (pinfunction "2_2") (pintype "input"))
      (node (ref "K3") (pin "3") (pinfunction "3_3") (pintype "input"))
      (node (ref "U8") (pin "6") (pinfunction "-INB_6") (pintype "unspecified"))
      (node (ref "U8") (pin "7") (pinfunction "OUTB_7") (pintype "unspecified"))
    )
    (net (code "31") (name "CH1_1030HZ_A") (class "Default")
      (node (ref "C35") (pin "2") (pinfunction "2_2") (pintype "input"))
      (node (ref "K2") (pin "3") (pinfunction "3_3") (pintype "input"))
      (node (ref "U8") (pin "1") (pinfunction "OUTA_1") (pintype "unspecified"))
      (node (ref "U8") (pin "2") (pinfunction "-INA_2") (pintype "unspecified"))
    )
    (net (code "32") (name "CH1_2030HZ_A") (class "Default")
      (node (ref "C32") (pin "1") (pinfunction "1_1") (pintype "input"))
      (node (ref "K1") (pin "3") (pinfunction "3_3") (pintype "input"))
      (node (ref "U8") (pin "8") (pinfunction "OUTC_8") (pintype "unspecified"))
      (node (ref "U8") (pin "9") (pinfunction "-INC_9") (pintype "unspecified"))
    )
    (net (code "33") (name "CH1_A") (class "Default")
      (node (ref "K8") (pin "2") (pinfunction "2_2") (pintype "input"))
      (node (ref "R21") (pin "1") (pinfunction "1_1") (pintype "input"))
      (node (ref "R24") (pin "2") (pinfunction "2_2") (pintype "input"))
      (node (ref "R26") (pin "2") (pinfunction "2_2") (pintype "input"))
      (node (ref "R27") (pin "1") (pinfunction "1_1") (pintype "input"))
      (node (ref "R29") (pin "1") (pinfunction "1_1") (pintype "input"))
      (node (ref "R32") (pin "2") (pinfunction "2_2") (pintype "input"))
      (node (ref "R35") (pin "1") (pinfunction "1_1") (pintype "input"))
    )
    (net (code "34") (name "CH1_FILTER_A") (class "Default")
      (node (ref "K1") (pin "4") (pinfunction "4_4") (pintype "input"))
      (node (ref "K2") (pin "4") (pinfunction "4_4") (pintype "input"))
      (node (ref "K3") (pin "4") (pinfunction "4_4") (pintype "input"))
      (node (ref "K4") (pin "4") (pinfunction "4_4") (pintype "input"))
      (node (ref "K5") (pin "4") (pinfunction "4_4") (pintype "input"))
      (node (ref "K6") (pin "4") (pinfunction "4_4") (pintype "input"))
      (node (ref "K7") (pin "4") (pinfunction "4_4") (pintype "input"))
      (node (ref "K8") (pin "4") (pinfunction "4_4") (pintype "input"))
      (node (ref "K9") (pin "2") (pinfunction "2_2") (pintype "input"))
      (node (ref "R34") (pin "2") (pinfunction "2_2") (pintype "input"))
      (node (ref "R53") (pin "2") (pinfunction "2_2") (pintype "unspecified"))
    )
    (net (code "35") (name "CH1_FILTER_C") (class "Default")
      (node (ref "K9") (pin "7") (pinfunction "7_7") (pintype "input"))
      (node (ref "R33") (pin "1") (pinfunction "1_1") (pintype "input"))
      (node (ref "R57") (pin "2") (pinfunction "2_2") (pintype "unspecified"))
      (node (ref "U8") (pin "14") (pinfunction "OUTD_14") (pintype "unspecified"))
    )
    (net (code "36") (name "CH1_INPUT") (class "Default")
      (node (ref "CN3") (pin "1") (pinfunction "1_1") (pintype "unspecified"))
      (node (ref "K8") (pin "3") (pinfunction "3_3") (pintype "input"))
    )
    (net (code "37") (name "CH2_2HZ_A") (class "Default")
      (node (ref "C39") (pin "2") (pinfunction "2_2") (pintype "unspecified"))
      (node (ref "K7") (pin "6") (pinfunction "6_6") (pintype "input"))
      (node (ref "U9") (pin "6") (pinfunction "-INB_6") (pintype "unspecified"))
      (node (ref "U9") (pin "7") (pinfunction "OUTB_7") (pintype "unspecified"))
    )
    (net (code "38") (name "CH2_8HZ_A") (class "Default")
      (node (ref "C43") (pin "2") (pinfunction "2_2") (pintype "unspecified"))
      (node (ref "K6") (pin "6") (pinfunction "6_6") (pintype "input"))
      (node (ref "U9") (pin "1") (pinfunction "OUTA_1") (pintype "unspecified"))
      (node (ref "U9") (pin "2") (pinfunction "-INA_2") (pintype "unspecified"))
    )
    (net (code "39") (name "CH2_40HZ_A") (class "Default")
      (node (ref "C40") (pin "1") (pinfunction "1_1") (pintype "unspecified"))
      (node (ref "K5") (pin "6") (pinfunction "6_6") (pintype "input"))
      (node (ref "U9") (pin "8") (pinfunction "OUTC_8") (pintype "unspecified"))
      (node (ref "U9") (pin "9") (pinfunction "-INC_9") (pintype "unspecified"))
    )
    (net (code "40") (name "CH2_130HZ_A") (class "Default")
      (node (ref "C46") (pin "1") (pinfunction "1_1") (pintype "input"))
      (node (ref "K4") (pin "6") (pinfunction "6_6") (pintype "input"))
      (node (ref "U9") (pin "14") (pinfunction "OUTD_14") (pintype "unspecified"))
    )
    (net (code "41") (name "CH2_530HZ_A") (class "Default")
      (node (ref "C49") (pin "2") (pinfunction "2_2") (pintype "input"))
      (node (ref "K3") (pin "6") (pinfunction "6_6") (pintype "input"))
      (node (ref "U10") (pin "6") (pinfunction "-INB_6") (pintype "unspecified"))
      (node (ref "U10") (pin "7") (pinfunction "OUTB_7") (pintype "unspecified"))
    )
    (net (code "42") (name "CH2_1030HZ_A") (class "Default")
      (node (ref "C53") (pin "2") (pinfunction "2_2") (pintype "input"))
      (node (ref "K2") (pin "6") (pinfunction "6_6") (pintype "input"))
      (node (ref "U10") (pin "1") (pinfunction "OUTA_1") (pintype "unspecified"))
      (node (ref "U10") (pin "2") (pinfunction "-INA_2") (pintype "unspecified"))
    )
    (net (code "43") (name "CH2_2030HZ_A") (class "Default")
      (node (ref "C50") (pin "1") (pinfunction "1_1") (pintype "input"))
      (node (ref "K1") (pin "6") (pinfunction "6_6") (pintype "input"))
      (node (ref "U10") (pin "8") (pinfunction "OUTC_8") (pintype "unspecified"))
      (node (ref "U10") (pin "9") (pinfunction "-INC_9") (pintype "unspecified"))
    )
    (net (code "44") (name "CH2_A") (class "Default")
      (node (ref "K8") (pin "7") (pinfunction "7_7") (pintype "input"))
      (node (ref "R37") (pin "1") (pinfunction "1_1") (pintype "input"))
      (node (ref "R40") (pin "2") (pinfunction "2_2") (pintype "input"))
      (node (ref "R42") (pin "2") (pinfunction "2_2") (pintype "input"))
      (node (ref "R43") (pin "1") (pinfunction "1_1") (pintype "input"))
      (node (ref "R45") (pin "1") (pinfunction "1_1") (pintype "input"))
      (node (ref "R48") (pin "2") (pinfunction "2_2") (pintype "input"))
      (node (ref "R51") (pin "1") (pinfunction "1_1") (pintype "input"))
    )
    (net (code "45") (name "CH2_FILTER_A") (class "Default")
      (node (ref "K1") (pin "5") (pinfunction "5_5") (pintype "input"))
      (node (ref "K10") (pin "2") (pinfunction "2_2") (pintype "input"))
      (node (ref "K2") (pin "5") (pinfunction "5_5") (pintype "input"))
      (node (ref "K3") (pin "5") (pinfunction "5_5") (pintype "input"))
      (node (ref "K4") (pin "5") (pinfunction "5_5") (pintype "input"))
      (node (ref "K5") (pin "5") (pinfunction "5_5") (pintype "input"))
      (node (ref "K6") (pin "5") (pinfunction "5_5") (pintype "input"))
      (node (ref "K7") (pin "5") (pinfunction "5_5") (pintype "input"))
      (node (ref "K8") (pin "5") (pinfunction "5_5") (pintype "input"))
      (node (ref "R50") (pin "2") (pinfunction "2_2") (pintype "input"))
      (node (ref "R54") (pin "2") (pinfunction "2_2") (pintype "unspecified"))
    )
    (net (code "46") (name "CH2_FILTER_C") (class "Default")
      (node (ref "K10") (pin "7") (pinfunction "7_7") (pintype "input"))
      (node (ref "R49") (pin "1") (pinfunction "1_1") (pintype "input"))
      (node (ref "R58") (pin "2") (pinfunction "2_2") (pintype "unspecified"))
      (node (ref "U10") (pin "14") (pinfunction "OUTD_14") (pintype "unspecified"))
    )
    (net (code "47") (name "CH2_INPUT") (class "Default")
      (node (ref "CN4") (pin "1") (pinfunction "1_1") (pintype "unspecified"))
      (node (ref "K8") (pin "6") (pinfunction "6_6") (pintype "input"))
    )
    (net (code "48") (name "CS1") (class "Default")
      (node (ref "U5") (pin "23") (pinfunction "CSB_23") (pintype "unspecified"))
      (node (ref "U6") (pin "9") (pinfunction "PA3_9") (pintype "unspecified"))
    )
    (net (code "49") (name "CS2") (class "Default")
      (node (ref "U12") (pin "23") (pinfunction "CSB_23") (pintype "unspecified"))
      (node (ref "U6") (pin "10") (pinfunction "PA4_10") (pintype "unspecified"))
    )
    (net (code "50") (name "EN") (class "Default")
      (node (ref "U12") (pin "21") (pinfunction "EN_21") (pintype "unspecified"))
      (node (ref "U5") (pin "21") (pinfunction "EN_21") (pintype "unspecified"))
      (node (ref "U6") (pin "14") (pinfunction "PB1_14") (pintype "unspecified"))
    )
    (net (code "51") (name "G") (class "Default")
      (node (ref "CN5") (pin "19") (pinfunction "19_19") (pintype "unspecified"))
      (node (ref "CN5") (pin "20") (pinfunction "20_20") (pintype "unspecified"))
      (node (ref "SW1") (pin "2") (pinfunction "2_2") (pintype "input"))
      (node (ref "SW2") (pin "4") (pinfunction "4_4") (pintype "unspecified"))
    )
    (net (code "52") (name "GND") (class "Default")
      (node (ref "C1") (pin "2") (pinfunction "2_2") (pintype "input"))
      (node (ref "C10") (pin "1") (pinfunction "1_1") (pintype "input"))
      (node (ref "C12") (pin "1") (pinfunction "1_1") (pintype "input"))
      (node (ref "C13") (pin "2") (pinfunction "2_2") (pintype "input"))
      (node (ref "C14") (pin "2") (pinfunction "2_2") (pintype "input"))
      (node (ref "C15") (pin "1") (pinfunction "1_1") (pintype "input"))
      (node (ref "C16") (pin "2") (pinfunction "2_2") (pintype "input"))
      (node (ref "C17") (pin "1") (pinfunction "1_1") (pintype "input"))
      (node (ref "C18") (pin "1") (pinfunction "1_1") (pintype "input"))
      (node (ref "C2") (pin "1") (pinfunction "1_1") (pintype "input"))
      (node (ref "C23") (pin "1") (pinfunction "1_1") (pintype "unspecified"))
      (node (ref "C24") (pin "2") (pinfunction "2_2") (pintype "input"))
      (node (ref "C26") (pin "1") (pinfunction "1_1") (pintype "input"))
      (node (ref "C27") (pin "1") (pinfunction "1_1") (pintype "unspecified"))
      (node (ref "C3") (pin "1") (pinfunction "1_1") (pintype "unspecified"))
      (node (ref "C33") (pin "1") (pinfunction "1_1") (pintype "input"))
      (node (ref "C34") (pin "2") (pinfunction "2_2") (pintype "input"))
      (node (ref "C36") (pin "1") (pinfunction "1_1") (pintype "input"))
      (node (ref "C4") (pin "1") (pinfunction "1_1") (pintype "input"))
      (node (ref "C41") (pin "1") (pinfunction "1_1") (pintype "unspecified"))
      (node (ref "C42") (pin "2") (pinfunction "2_2") (pintype "input"))
      (node (ref "C44") (pin "1") (pinfunction "1_1") (pintype "input"))
      (node (ref "C45") (pin "1") (pinfunction "1_1") (pintype "unspecified"))
      (node (ref "C51") (pin "1") (pinfunction "1_1") (pintype "input"))
      (node (ref "C52") (pin "2") (pinfunction "2_2") (pintype "input"))
      (node (ref "C54") (pin "1") (pinfunction "1_1") (pintype "input"))
      (node (ref "C6") (pin "1") (pinfunction "1_1") (pintype "input"))
      (node (ref "C7") (pin "1") (pinfunction "1_1") (pintype "input"))
      (node (ref "C8") (pin "1") (pinfunction "1_1") (pintype "input"))
      (node (ref "C9") (pin "1") (pinfunction "1_1") (pintype "input"))
      (node (ref "CN1") (pin "2") (pinfunction "2_2") (pintype "unspecified"))
      (node (ref "CN2") (pin "5") (pinfunction "5_5") (pintype "unspecified"))
      (node (ref "CN2") (pin "7") (pinfunction "7_7") (pintype "unspecified"))
      (node (ref "CN3") (pin "2") (pinfunction "2_2") (pintype "unspecified"))
      (node (ref "CN4") (pin "2") (pinfunction "2_2") (pintype "unspecified"))
      (node (ref "CN6") (pin "2") (pinfunction "2_2") (pintype "unspecified"))
      (node (ref "R17") (pin "2") (pinfunction "2_2") (pintype "input"))
      (node (ref "R18") (pin "1") (pinfunction "1_1") (pintype "input"))
      (node (ref "R19") (pin "1") (pinfunction "1_1") (pintype "input"))
      (node (ref "R2") (pin "1") (pinfunction "1_1") (pintype "input"))
      (node (ref "R20") (pin "1") (pinfunction "1_1") (pintype "input"))
      (node (ref "R3") (pin "1") (pinfunction "1_1") (pintype "input"))
      (node (ref "R4") (pin "1") (pinfunction "1_1") (pintype "input"))
      (node (ref "R5") (pin "1") (pinfunction "1_1") (pintype "input"))
      (node (ref "R55") (pin "1") (pinfunction "1_1") (pintype "input"))
      (node (ref "R56") (pin "1") (pinfunction "1_1") (pintype "input"))
      (node (ref "R59") (pin "1") (pinfunction "1_1") (pintype "input"))
      (node (ref "R6") (pin "1") (pinfunction "1_1") (pintype "input"))
      (node (ref "R60") (pin "1") (pinfunction "1_1") (pintype "input"))
      (node (ref "R68") (pin "1") (pinfunction "1_1") (pintype "input"))
      (node (ref "R69") (pin "1") (pinfunction "1_1") (pintype "input"))
      (node (ref "R72") (pin "1") (pinfunction "1_1") (pintype "input"))
      (node (ref "R73") (pin "1") (pinfunction "1_1") (pintype "input"))
      (node (ref "R75") (pin "1") (pinfunction "1_1") (pintype "input"))
      (node (ref "R8") (pin "1") (pinfunction "1_1") (pintype "input"))
      (node (ref "SW2") (pin "2") (pinfunction "2_2") (pintype "unspecified"))
      (node (ref "U1") (pin "4") (pinfunction "GND_4") (pintype "unspecified"))
      (node (ref "U1") (pin "9") (pinfunction "PwPd_9") (pintype "unspecified"))
      (node (ref "U10") (pin "12") (pinfunction "+IND_12") (pintype "unspecified"))
      (node (ref "U12") (pin "1") (pinfunction "GND_1") (pintype "unspecified"))
      (node (ref "U12") (pin "11") (pinfunction "GND_11") (pintype "unspecified"))
      (node (ref "U12") (pin "12") (pinfunction "GND_12") (pintype "unspecified"))
      (node (ref "U12") (pin "14") (pinfunction "IN4_14") (pintype "unspecified"))
      (node (ref "U12") (pin "15") (pinfunction "IN3_15") (pintype "unspecified"))
      (node (ref "U12") (pin "16") (pinfunction "IN2_16") (pintype "unspecified"))
      (node (ref "U12") (pin "17") (pinfunction "IN1_17") (pintype "unspecified"))
      (node (ref "U12") (pin "18") (pinfunction "LHI_18") (pintype "unspecified"))
      (node (ref "U12") (pin "2") (pinfunction "GND_2") (pintype "unspecified"))
      (node (ref "U14") (pin "1") (pinfunction "1_1") (pintype "unspecified"))
      (node (ref "U14") (pin "36") (pinfunction "36_36") (pintype "unspecified"))
      (node (ref "U2") (pin "15") (pinfunction "PGND_15") (pintype "unspecified"))
      (node (ref "U2") (pin "16") (pinfunction "PGND_16") (pintype "unspecified"))
      (node (ref "U2") (pin "17") (pinfunction "EP_17") (pintype "unspecified"))
      (node (ref "U2") (pin "5") (pinfunction "FB_5") (pintype "unspecified"))
      (node (ref "U2") (pin "6") (pinfunction "AGND_6") (pintype "unspecified"))
      (node (ref "U2") (pin "7") (pinfunction "FSW_7") (pintype "unspecified"))
      (node (ref "U2") (pin "8") (pinfunction "DEF_8") (pintype "unspecified"))
      (node (ref "U3") (pin "4") (pinfunction "GND_4") (pintype "unspecified"))
      (node (ref "U3") (pin "9") (pinfunction "EP_9") (pintype "unspecified"))
      (node (ref "U4") (pin "2") (pinfunction "GND_2") (pintype "unspecified"))
      (node (ref "U5") (pin "1") (pinfunction "GND_1") (pintype "unspecified"))
      (node (ref "U5") (pin "11") (pinfunction "GND_11") (pintype "unspecified"))
      (node (ref "U5") (pin "12") (pinfunction "GND_12") (pintype "unspecified"))
      (node (ref "U5") (pin "14") (pinfunction "IN4_14") (pintype "unspecified"))
      (node (ref "U5") (pin "15") (pinfunction "IN3_15") (pintype "unspecified"))
      (node (ref "U5") (pin "16") (pinfunction "IN2_16") (pintype "unspecified"))
      (node (ref "U5") (pin "17") (pinfunction "IN1_17") (pintype "unspecified"))
      (node (ref "U5") (pin "18") (pinfunction "LHI_18") (pintype "unspecified"))
      (node (ref "U5") (pin "2") (pinfunction "GND_2") (pintype "unspecified"))
      (node (ref "U6") (pin "15") (pinfunction "VSS_15") (pintype "unspecified"))
      (node (ref "U8") (pin "12") (pinfunction "+IND_12") (pintype "unspecified"))
      (node (ref "USB1") (pin "1") (pinfunction "SHELL_1") (pintype "unspecified"))
      (node (ref "USB1") (pin "2") (pinfunction "SHELL_2") (pintype "unspecified"))
      (node (ref "USB1") (pin "3") (pinfunction "SHELL_3") (pintype "unspecified"))
      (node (ref "USB1") (pin "4") (pinfunction "SHELL_4") (pintype "unspecified"))
      (node (ref "USB1") (pin "A1B12") (pinfunction "GND_A1B12") (pintype "unspecified"))
      (node (ref "USB1") (pin "B1A12") (pinfunction "GND_B1A12") (pintype "unspecified"))
    )
    (net (code "53") (name "NRST") (class "Default")
      (node (ref "CN2") (pin "12") (pinfunction "12_12") (pintype "unspecified"))
      (node (ref "U6") (pin "4") (pinfunction "NRST_4") (pintype "unspecified"))
    )
    (net (code "54") (name "Net-(C21-Pad1)") (class "Default")
      (node (ref "C21") (pin "1") (pinfunction "1_1") (pintype "unspecified"))
      (node (ref "R21") (pin "2") (pinfunction "2_2") (pintype "input"))
      (node (ref "R22") (pin "1") (pinfunction "1_1") (pintype "input"))
    )
    (net (code "55") (name "Net-(C22-Pad2)") (class "Default")
      (node (ref "C22") (pin "2") (pinfunction "2_2") (pintype "unspecified"))
      (node (ref "R23") (pin "2") (pinfunction "2_2") (pintype "input"))
      (node (ref "R24") (pin "1") (pinfunction "1_1") (pintype "input"))
    )
    (net (code "56") (name "Net-(C25-Pad1)") (class "Default")
      (node (ref "C25") (pin "1") (pinfunction "1_1") (pintype "unspecified"))
      (node (ref "R27") (pin "2") (pinfunction "2_2") (pintype "input"))
      (node (ref "R28") (pin "1") (pinfunction "1_1") (pintype "input"))
    )
    (net (code "57") (name "Net-(C28-Pad2)") (class "Default")
      (node (ref "C28") (pin "2") (pinfunction "2_2") (pintype "input"))
      (node (ref "R25") (pin "2") (pinfunction "2_2") (pintype "input"))
      (node (ref "R26") (pin "1") (pinfunction "1_1") (pintype "input"))
    )
    (net (code "58") (name "Net-(C31-Pad1)") (class "Default")
      (node (ref "C31") (pin "1") (pinfunction "1_1") (pintype "input"))
      (node (ref "R29") (pin "2") (pinfunction "2_2") (pintype "input"))
      (node (ref "R30") (pin "1") (pinfunction "1_1") (pintype "input"))
    )
    (net (code "59") (name "Net-(C32-Pad2)") (class "Default")
      (node (ref "C32") (pin "2") (pinfunction "2_2") (pintype "input"))
      (node (ref "R31") (pin "2") (pinfunction "2_2") (pintype "input"))
      (node (ref "R32") (pin "1") (pinfunction "1_1") (pintype "input"))
    )
    (net (code "60") (name "Net-(C35-Pad1)") (class "Default")
      (node (ref "C35") (pin "1") (pinfunction "1_1") (pintype "input"))
      (node (ref "R35") (pin "2") (pinfunction "2_2") (pintype "input"))
      (node (ref "R36") (pin "1") (pinfunction "1_1") (pintype "input"))
    )
    (net (code "61") (name "Net-(C39-Pad1)") (class "Default")
      (node (ref "C39") (pin "1") (pinfunction "1_1") (pintype "unspecified"))
      (node (ref "R37") (pin "2") (pinfunction "2_2") (pintype "input"))
      (node (ref "R38") (pin "1") (pinfunction "1_1") (pintype "input"))
    )
    (net (code "62") (name "Net-(C40-Pad2)") (class "Default")
      (node (ref "C40") (pin "2") (pinfunction "2_2") (pintype "unspecified"))
      (node (ref "R39") (pin "2") (pinfunction "2_2") (pintype "input"))
      (node (ref "R40") (pin "1") (pinfunction "1_1") (pintype "input"))
    )
    (net (code "63") (name "Net-(C43-Pad1)") (class "Default")
      (node (ref "C43") (pin "1") (pinfunction "1_1") (pintype "unspecified"))
      (node (ref "R43") (pin "2") (pinfunction "2_2") (pintype "input"))
      (node (ref "R44") (pin "1") (pinfunction "1_1") (pintype "input"))
    )
    (net (code "64") (name "Net-(C46-Pad2)") (class "Default")
      (node (ref "C46") (pin "2") (pinfunction "2_2") (pintype "input"))
      (node (ref "R41") (pin "2") (pinfunction "2_2") (pintype "input"))
      (node (ref "R42") (pin "1") (pinfunction "1_1") (pintype "input"))
    )
    (net (code "65") (name "Net-(C49-Pad1)") (class "Default")
      (node (ref "C49") (pin "1") (pinfunction "1_1") (pintype "input"))
      (node (ref "R45") (pin "2") (pinfunction "2_2") (pintype "input"))
      (node (ref "R46") (pin "1") (pinfunction "1_1") (pintype "input"))
    )
    (net (code "66") (name "Net-(C50-Pad2)") (class "Default")
      (node (ref "C50") (pin "2") (pinfunction "2_2") (pintype "input"))
      (node (ref "R47") (pin "2") (pinfunction "2_2") (pintype "input"))
      (node (ref "R48") (pin "1") (pinfunction "1_1") (pintype "input"))
    )
    (net (code "67") (name "Net-(C53-Pad1)") (class "Default")
      (node (ref "C53") (pin "1") (pinfunction "1_1") (pintype "input"))
      (node (ref "R51") (pin "2") (pinfunction "2_2") (pintype "input"))
      (node (ref "R52") (pin "1") (pinfunction "1_1") (pintype "input"))
    )
    (net (code "68") (name "Net-(CN2-Pad11)") (class "Default")
      (node (ref "CN2") (pin "11") (pinfunction "11_11") (pintype "unspecified"))
      (node (ref "R18") (pin "2") (pinfunction "2_2") (pintype "input"))
    )
    (net (code "69") (name "Net-(L1-Pad1)") (class "Default")
      (node (ref "L1") (pin "1") (pinfunction "1_1") (pintype "unspecified"))
      (node (ref "U2") (pin "1") (pinfunction "SW_1") (pintype "unspecified"))
      (node (ref "U2") (pin "2") (pinfunction "SW_2") (pintype "unspecified"))
      (node (ref "U2") (pin "3") (pinfunction "SW_3") (pintype "unspecified"))
    )
    (net (code "70") (name "Net-(LED1-K)") (class "Default")
      (node (ref "LED1") (pin "1") (pinfunction "K_1") (pintype "unspecified"))
      (node (ref "R3") (pin "2") (pinfunction "2_2") (pintype "input"))
    )
    (net (code "71") (name "Net-(LED2-K)") (class "Default")
      (node (ref "LED2") (pin "1") (pinfunction "K_1") (pintype "unspecified"))
      (node (ref "R4") (pin "2") (pinfunction "2_2") (pintype "input"))
    )
    (net (code "72") (name "Net-(LED3-K)") (class "Default")
      (node (ref "LED3") (pin "1") (pinfunction "K_1") (pintype "unspecified"))
      (node (ref "R5") (pin "2") (pinfunction "2_2") (pintype "input"))
    )
    (net (code "73") (name "Net-(LED4-A)") (class "Default")
      (node (ref "LED4") (pin "2") (pinfunction "A_2") (pintype "unspecified"))
      (node (ref "R6") (pin "2") (pinfunction "2_2") (pintype "input"))
    )
    (net (code "74") (name "Net-(LED5-A)") (class "Default")
      (node (ref "LED5") (pin "2") (pinfunction "A_2") (pintype "unspecified"))
      (node (ref "R9") (pin "1") (pinfunction "1_1") (pintype "input"))
    )
    (net (code "75") (name "Net-(LED6-A)") (class "Default")
      (node (ref "LED6") (pin "2") (pinfunction "A_2") (pintype "unspecified"))
      (node (ref "R11") (pin "1") (pinfunction "1_1") (pintype "input"))
    )
    (net (code "76") (name "Net-(LED7-A)") (class "Default")
      (node (ref "LED7") (pin "2") (pinfunction "A_2") (pintype "unspecified"))
      (node (ref "R10") (pin "1") (pinfunction "1_1") (pintype "input"))
    )
    (net (code "77") (name "Net-(LED8-A)") (class "Default")
      (node (ref "LED8") (pin "2") (pinfunction "A_2") (pintype "unspecified"))
      (node (ref "R13") (pin "1") (pinfunction "1_1") (pintype "input"))
    )
    (net (code "78") (name "Net-(LED9-A)") (class "Default")
      (node (ref "LED9") (pin "2") (pinfunction "A_2") (pintype "unspecified"))
      (node (ref "R12") (pin "1") (pinfunction "1_1") (pintype "input"))
    )
    (net (code "79") (name "Net-(LED10-A)") (class "Default")
      (node (ref "LED10") (pin "2") (pinfunction "A_2") (pintype "unspecified"))
      (node (ref "R15") (pin "1") (pinfunction "1_1") (pintype "input"))
    )
    (net (code "80") (name "Net-(LED11-A)") (class "Default")
      (node (ref "LED11") (pin "2") (pinfunction "A_2") (pintype "unspecified"))
      (node (ref "R14") (pin "1") (pinfunction "1_1") (pintype "input"))
    )
    (net (code "81") (name "Net-(LED12-A)") (class "Default")
      (node (ref "LED12") (pin "2") (pinfunction "A_2") (pintype "unspecified"))
      (node (ref "R16") (pin "1") (pinfunction "1_1") (pintype "input"))
    )
    (net (code "82") (name "Net-(LED13-A)") (class "Default")
      (node (ref "LED13") (pin "2") (pinfunction "A_2") (pintype "unspecified"))
      (node (ref "R61") (pin "1") (pinfunction "1_1") (pintype "input"))
    )
    (net (code "83") (name "Net-(LED14-A)") (class "Default")
      (node (ref "LED14") (pin "2") (pinfunction "A_2") (pintype "unspecified"))
      (node (ref "R62") (pin "1") (pinfunction "1_1") (pintype "input"))
    )
    (net (code "84") (name "Net-(LED15-A)") (class "Default")
      (node (ref "LED15") (pin "2") (pinfunction "A_2") (pintype "unspecified"))
      (node (ref "R63") (pin "1") (pinfunction "1_1") (pintype "input"))
    )
    (net (code "85") (name "Net-(LED16-A)") (class "Default")
      (node (ref "LED16") (pin "2") (pinfunction "A_2") (pintype "unspecified"))
      (node (ref "R65") (pin "1") (pinfunction "1_1") (pintype "input"))
    )
    (net (code "86") (name "Net-(LED17-A)") (class "Default")
      (node (ref "LED17") (pin "2") (pinfunction "A_2") (pintype "unspecified"))
      (node (ref "R64") (pin "1") (pinfunction "1_1") (pintype "input"))
    )
    (net (code "87") (name "Net-(U1-FB)") (class "Default")
      (node (ref "C5") (pin "1") (pinfunction "1_1") (pintype "input"))
      (node (ref "R1") (pin "1") (pinfunction "1_1") (pintype "input"))
      (node (ref "R2") (pin "2") (pinfunction "2_2") (pintype "input"))
      (node (ref "U1") (pin "2") (pinfunction "FB_2") (pintype "unspecified"))
    )
    (net (code "88") (name "Net-(U1-NR{slash}SS)") (class "Default")
      (node (ref "C8") (pin "2") (pinfunction "2_2") (pintype "input"))
      (node (ref "U1") (pin "6") (pinfunction "NR/SS_6") (pintype "unspecified"))
    )
    (net (code "89") (name "Net-(U2-SS{slash}TR)") (class "Default")
      (node (ref "C9") (pin "2") (pinfunction "2_2") (pintype "input"))
      (node (ref "U2") (pin "9") (pinfunction "SS/TR_9") (pintype "unspecified"))
    )
    (net (code "90") (name "Net-(U3-FB)") (class "Default")
      (node (ref "C11") (pin "1") (pinfunction "1_1") (pintype "input"))
      (node (ref "R7") (pin "1") (pinfunction "1_1") (pintype "input"))
      (node (ref "R8") (pin "2") (pinfunction "2_2") (pintype "input"))
      (node (ref "U3") (pin "2") (pinfunction "FB_2") (pintype "unspecified"))
    )
    (net (code "91") (name "Net-(U3-NRSS)") (class "Default")
      (node (ref "C15") (pin "2") (pinfunction "2_2") (pintype "input"))
      (node (ref "U3") (pin "6") (pinfunction "NRSS_6") (pintype "unspecified"))
    )
    (net (code "92") (name "Net-(U6-BOOT0)") (class "Default")
      (node (ref "R17") (pin "1") (pinfunction "1_1") (pintype "input"))
      (node (ref "U6") (pin "1") (pinfunction "BOOT0_1") (pintype "unspecified"))
    )
    (net (code "93") (name "Net-(U6-PF0{slash}OSC_IN)") (class "Default")
      (node (ref "U6") (pin "2") (pinfunction "PF0/OSC_IN_2") (pintype "unspecified"))
      (node (ref "X1") (pin "1") (pinfunction "1_1") (pintype "input"))
    )
    (net (code "94") (name "Net-(U6-PF1{slash}OSC_OUT)") (class "Default")
      (node (ref "U6") (pin "3") (pinfunction "PF1/OSC_OUT_3") (pintype "unspecified"))
      (node (ref "X1") (pin "3") (pinfunction "3_3") (pintype "input"))
    )
    (net (code "95") (name "Net-(U7-+INA)") (class "Default")
      (node (ref "C27") (pin "2") (pinfunction "2_2") (pintype "unspecified"))
      (node (ref "R28") (pin "2") (pinfunction "2_2") (pintype "input"))
      (node (ref "U7") (pin "3") (pinfunction "+INA_3") (pintype "unspecified"))
    )
    (net (code "96") (name "Net-(U7-+INB)") (class "Default")
      (node (ref "C23") (pin "2") (pinfunction "2_2") (pintype "unspecified"))
      (node (ref "R22") (pin "2") (pinfunction "2_2") (pintype "input"))
      (node (ref "U7") (pin "5") (pinfunction "+INB_5") (pintype "unspecified"))
    )
    (net (code "97") (name "Net-(U7-+INC)") (class "Default")
      (node (ref "C24") (pin "1") (pinfunction "1_1") (pintype "input"))
      (node (ref "R23") (pin "1") (pinfunction "1_1") (pintype "input"))
      (node (ref "U7") (pin "10") (pinfunction "+INC_10") (pintype "unspecified"))
    )
    (net (code "98") (name "Net-(U7-+IND)") (class "Default")
      (node (ref "C26") (pin "2") (pinfunction "2_2") (pintype "input"))
      (node (ref "R25") (pin "1") (pinfunction "1_1") (pintype "input"))
      (node (ref "U7") (pin "12") (pinfunction "+IND_12") (pintype "unspecified"))
    )
    (net (code "99") (name "Net-(U8-+INA)") (class "Default")
      (node (ref "C36") (pin "2") (pinfunction "2_2") (pintype "input"))
      (node (ref "R36") (pin "2") (pinfunction "2_2") (pintype "input"))
      (node (ref "U8") (pin "3") (pinfunction "+INA_3") (pintype "unspecified"))
    )
    (net (code "100") (name "Net-(U8-+INB)") (class "Default")
      (node (ref "C33") (pin "2") (pinfunction "2_2") (pintype "input"))
      (node (ref "R30") (pin "2") (pinfunction "2_2") (pintype "input"))
      (node (ref "U8") (pin "5") (pinfunction "+INB_5") (pintype "unspecified"))
    )
    (net (code "101") (name "Net-(U8-+INC)") (class "Default")
      (node (ref "C34") (pin "1") (pinfunction "1_1") (pintype "input"))
      (node (ref "R31") (pin "1") (pinfunction "1_1") (pintype "input"))
      (node (ref "U8") (pin "10") (pinfunction "+INC_10") (pintype "unspecified"))
    )
    (net (code "102") (name "Net-(U8--IND)") (class "Default")
      (node (ref "R33") (pin "2") (pinfunction "2_2") (pintype "input"))
      (node (ref "R34") (pin "1") (pinfunction "1_1") (pintype "input"))
      (node (ref "U8") (pin "13") (pinfunction "-IND_13") (pintype "unspecified"))
    )
    (net (code "103") (name "Net-(U9-+INA)") (class "Default")
      (node (ref "C45") (pin "2") (pinfunction "2_2") (pintype "unspecified"))
      (node (ref "R44") (pin "2") (pinfunction "2_2") (pintype "input"))
      (node (ref "U9") (pin "3") (pinfunction "+INA_3") (pintype "unspecified"))
    )
    (net (code "104") (name "Net-(U9-+INB)") (class "Default")
      (node (ref "C41") (pin "2") (pinfunction "2_2") (pintype "unspecified"))
      (node (ref "R38") (pin "2") (pinfunction "2_2") (pintype "input"))
      (node (ref "U9") (pin "5") (pinfunction "+INB_5") (pintype "unspecified"))
    )
    (net (code "105") (name "Net-(U9-+INC)") (class "Default")
      (node (ref "C42") (pin "1") (pinfunction "1_1") (pintype "input"))
      (node (ref "R39") (pin "1") (pinfunction "1_1") (pintype "input"))
      (node (ref "U9") (pin "10") (pinfunction "+INC_10") (pintype "unspecified"))
    )
    (net (code "106") (name "Net-(U9-+IND)") (class "Default")
      (node (ref "C44") (pin "2") (pinfunction "2_2") (pintype "input"))
      (node (ref "R41") (pin "1") (pinfunction "1_1") (pintype "input"))
      (node (ref "U9") (pin "12") (pinfunction "+IND_12") (pintype "unspecified"))
    )
    (net (code "107") (name "Net-(U10-+INA)") (class "Default")
      (node (ref "C54") (pin "2") (pinfunction "2_2") (pintype "input"))
      (node (ref "R52") (pin "2") (pinfunction "2_2") (pintype "input"))
      (node (ref "U10") (pin "3") (pinfunction "+INA_3") (pintype "unspecified"))
    )
    (net (code "108") (name "Net-(U10-+INB)") (class "Default")
      (node (ref "C51") (pin "2") (pinfunction "2_2") (pintype "input"))
      (node (ref "R46") (pin "2") (pinfunction "2_2") (pintype "input"))
      (node (ref "U10") (pin "5") (pinfunction "+INB_5") (pintype "unspecified"))
    )
    (net (code "109") (name "Net-(U10-+INC)") (class "Default")
      (node (ref "C52") (pin "1") (pinfunction "1_1") (pintype "input"))
      (node (ref "R47") (pin "1") (pinfunction "1_1") (pintype "input"))
      (node (ref "U10") (pin "10") (pinfunction "+INC_10") (pintype "unspecified"))
    )
    (net (code "110") (name "Net-(U10--IND)") (class "Default")
      (node (ref "R49") (pin "2") (pinfunction "2_2") (pintype "input"))
      (node (ref "R50") (pin "1") (pinfunction "1_1") (pintype "input"))
      (node (ref "U10") (pin "13") (pinfunction "-IND_13") (pintype "unspecified"))
    )
    (net (code "111") (name "Net-(U11-+INA)") (class "Default")
      (node (ref "R53") (pin "1") (pinfunction "1_1") (pintype "unspecified"))
      (node (ref "R55") (pin "2") (pinfunction "2_2") (pintype "input"))
      (node (ref "U11") (pin "3") (pinfunction "+INA_3") (pintype "unspecified"))
    )
    (net (code "112") (name "Net-(U11-+INB)") (class "Default")
      (node (ref "R57") (pin "1") (pinfunction "1_1") (pintype "unspecified"))
      (node (ref "R59") (pin "2") (pinfunction "2_2") (pintype "input"))
      (node (ref "U11") (pin "5") (pinfunction "+INB_5") (pintype "unspecified"))
    )
    (net (code "113") (name "Net-(U11-+INC)") (class "Default")
      (node (ref "R58") (pin "1") (pinfunction "1_1") (pintype "unspecified"))
      (node (ref "R60") (pin "2") (pinfunction "2_2") (pintype "input"))
      (node (ref "U11") (pin "10") (pinfunction "+INC_10") (pintype "unspecified"))
    )
    (net (code "114") (name "Net-(U11-+IND)") (class "Default")
      (node (ref "R54") (pin "1") (pinfunction "1_1") (pintype "unspecified"))
      (node (ref "R56") (pin "2") (pinfunction "2_2") (pintype "input"))
      (node (ref "U11") (pin "12") (pinfunction "+IND_12") (pintype "unspecified"))
    )
    (net (code "115") (name "Net-(U13-+INA)") (class "Default")
      (node (ref "R66") (pin "1") (pinfunction "1_1") (pintype "input"))
      (node (ref "R68") (pin "2") (pinfunction "2_2") (pintype "input"))
      (node (ref "U13") (pin "3") (pinfunction "+INA_3") (pintype "unspecified"))
    )
    (net (code "116") (name "Net-(U13-+INB)") (class "Default")
      (node (ref "R70") (pin "1") (pinfunction "1_1") (pintype "input"))
      (node (ref "R72") (pin "2") (pinfunction "2_2") (pintype "input"))
      (node (ref "U13") (pin "5") (pinfunction "+INB_5") (pintype "unspecified"))
    )
    (net (code "117") (name "Net-(U13-+INC)") (class "Default")
      (node (ref "R71") (pin "1") (pinfunction "1_1") (pintype "input"))
      (node (ref "R73") (pin "2") (pinfunction "2_2") (pintype "input"))
      (node (ref "U13") (pin "10") (pinfunction "+INC_10") (pintype "unspecified"))
    )
    (net (code "118") (name "Net-(U13-+IND)") (class "Default")
      (node (ref "R67") (pin "1") (pinfunction "1_1") (pintype "input"))
      (node (ref "R69") (pin "2") (pinfunction "2_2") (pintype "input"))
      (node (ref "U13") (pin "12") (pinfunction "+IND_12") (pintype "unspecified"))
    )
    (net (code "119") (name "Net-(USB1-CC1)") (class "Default")
      (node (ref "R20") (pin "2") (pinfunction "2_2") (pintype "input"))
      (node (ref "USB1") (pin "A5") (pinfunction "CC1_A5") (pintype "unspecified"))
    )
    (net (code "120") (name "Net-(USB1-CC2)") (class "Default")
      (node (ref "R19") (pin "2") (pinfunction "2_2") (pintype "input"))
      (node (ref "USB1") (pin "B5") (pinfunction "CC2_B5") (pintype "unspecified"))
    )
    (net (code "121") (name "R") (class "Default")
      (node (ref "CN5") (pin "17") (pinfunction "17_17") (pintype "unspecified"))
      (node (ref "CN5") (pin "18") (pinfunction "18_18") (pintype "unspecified"))
      (node (ref "SW1") (pin "1") (pinfunction "A1_1") (pintype "input"))
      (node (ref "SW2") (pin "3") (pinfunction "3_3") (pintype "unspecified"))
    )
    (net (code "122") (name "REF") (class "Default")
      (node (ref "CN6") (pin "1") (pinfunction "1_1") (pintype "unspecified"))
      (node (ref "SW2") (pin "1") (pinfunction "1_1") (pintype "unspecified"))
      (node (ref "U14") (pin "2") (pinfunction "2_2") (pintype "unspecified"))
      (node (ref "U14") (pin "35") (pinfunction "35_35") (pintype "unspecified"))
    )
    (net (code "123") (name "REL1") (class "Default")
      (node (ref "K11") (pin "8") (pinfunction "8_8") (pintype "input"))
      (node (ref "LED13") (pin "1") (pinfunction "K_1") (pintype "unspecified"))
      (node (ref "U12") (pin "3") (pinfunction "OUT1_3") (pintype "unspecified"))
    )
    (net (code "124") (name "REL2") (class "Default")
      (node (ref "K12") (pin "8") (pinfunction "8_8") (pintype "input"))
      (node (ref "LED14") (pin "1") (pinfunction "K_1") (pintype "unspecified"))
      (node (ref "U12") (pin "4") (pinfunction "OUT2_4") (pintype "unspecified"))
    )
    (net (code "125") (name "REL3") (class "Default")
      (node (ref "K13") (pin "8") (pinfunction "8_8") (pintype "input"))
      (node (ref "LED15") (pin "1") (pinfunction "K_1") (pintype "unspecified"))
      (node (ref "U12") (pin "5") (pinfunction "OUT3_5") (pintype "unspecified"))
    )
    (net (code "126") (name "REL4") (class "Default")
      (node (ref "K9") (pin "8") (pinfunction "8_8") (pintype "input"))
      (node (ref "LED17") (pin "1") (pinfunction "K_1") (pintype "unspecified"))
      (node (ref "U12") (pin "6") (pinfunction "OUT4_6") (pintype "unspecified"))
    )
    (net (code "127") (name "REL5") (class "Default")
      (node (ref "K10") (pin "8") (pinfunction "8_8") (pintype "input"))
      (node (ref "LED16") (pin "1") (pinfunction "K_1") (pintype "unspecified"))
      (node (ref "U12") (pin "7") (pinfunction "OUT5_7") (pintype "unspecified"))
    )
    (net (code "128") (name "RELAY1") (class "Default")
      (node (ref "K8") (pin "8") (pinfunction "8_8") (pintype "input"))
      (node (ref "LED5") (pin "1") (pinfunction "K_1") (pintype "unspecified"))
      (node (ref "U5") (pin "3") (pinfunction "OUT1_3") (pintype "unspecified"))
    )
    (net (code "129") (name "RELAY2") (class "Default")
      (node (ref "K7") (pin "8") (pinfunction "8_8") (pintype "input"))
      (node (ref "LED7") (pin "1") (pinfunction "K_1") (pintype "unspecified"))
      (node (ref "U5") (pin "4") (pinfunction "OUT2_4") (pintype "unspecified"))
    )
    (net (code "130") (name "RELAY3") (class "Default")
      (node (ref "K6") (pin "8") (pinfunction "8_8") (pintype "input"))
      (node (ref "LED6") (pin "1") (pinfunction "K_1") (pintype "unspecified"))
      (node (ref "U5") (pin "5") (pinfunction "OUT3_5") (pintype "unspecified"))
    )
    (net (code "131") (name "RELAY4") (class "Default")
      (node (ref "K5") (pin "8") (pinfunction "8_8") (pintype "input"))
      (node (ref "LED9") (pin "1") (pinfunction "K_1") (pintype "unspecified"))
      (node (ref "U5") (pin "6") (pinfunction "OUT4_6") (pintype "unspecified"))
    )
    (net (code "132") (name "RELAY5") (class "Default")
      (node (ref "K4") (pin "8") (pinfunction "8_8") (pintype "input"))
      (node (ref "LED8") (pin "1") (pinfunction "K_1") (pintype "unspecified"))
      (node (ref "U5") (pin "7") (pinfunction "OUT5_7") (pintype "unspecified"))
    )
    (net (code "133") (name "RELAY6") (class "Default")
      (node (ref "K3") (pin "8") (pinfunction "8_8") (pintype "input"))
      (node (ref "LED11") (pin "1") (pinfunction "K_1") (pintype "unspecified"))
      (node (ref "U5") (pin "8") (pinfunction "OUT6_8") (pintype "unspecified"))
    )
    (net (code "134") (name "RELAY7") (class "Default")
      (node (ref "K2") (pin "8") (pinfunction "8_8") (pintype "input"))
      (node (ref "LED10") (pin "1") (pinfunction "K_1") (pintype "unspecified"))
      (node (ref "U5") (pin "9") (pinfunction "OUT7_9") (pintype "unspecified"))
    )
    (net (code "135") (name "RELAY8") (class "Default")
      (node (ref "K1") (pin "8") (pinfunction "8_8") (pintype "input"))
      (node (ref "LED12") (pin "1") (pinfunction "K_1") (pintype "unspecified"))
      (node (ref "U5") (pin "10") (pinfunction "OUT8_10") (pintype "unspecified"))
    )
    (net (code "136") (name "SCK") (class "Default")
      (node (ref "U12") (pin "20") (pinfunction "SCLK_20") (pintype "unspecified"))
      (node (ref "U5") (pin "20") (pinfunction "SCLK_20") (pintype "unspecified"))
      (node (ref "U6") (pin "11") (pinfunction "PA5_11") (pintype "unspecified"))
    )
    (net (code "137") (name "SEN_CH1") (class "Default")
      (node (ref "CN5") (pin "1") (pinfunction "1_1") (pintype "unspecified"))
      (node (ref "K11") (pin "6") (pinfunction "6_6") (pintype "input"))
    )
    (net (code "138") (name "SEN_CH2") (class "Default")
      (node (ref "CN5") (pin "2") (pinfunction "2_2") (pintype "unspecified"))
      (node (ref "U14") (pin "4") (pinfunction "4_4") (pintype "unspecified"))
    )
    (net (code "139") (name "SEN_CH3") (class "Default")
      (node (ref "CN5") (pin "3") (pinfunction "3_3") (pintype "unspecified"))
      (node (ref "U14") (pin "5") (pinfunction "5_5") (pintype "unspecified"))
    )
    (net (code "140") (name "SEN_CH4") (class "Default")
      (node (ref "CN5") (pin "4") (pinfunction "4_4") (pintype "unspecified"))
      (node (ref "K13") (pin "6") (pinfunction "6_6") (pintype "input"))
    )
    (net (code "141") (name "SEN_CH5") (class "Default")
      (node (ref "CN5") (pin "5") (pinfunction "5_5") (pintype "unspecified"))
      (node (ref "U14") (pin "7") (pinfunction "7_7") (pintype "unspecified"))
    )
    (net (code "142") (name "SEN_CH6") (class "Default")
      (node (ref "CN5") (pin "6") (pinfunction "6_6") (pintype "unspecified"))
      (node (ref "U14") (pin "8") (pinfunction "8_8") (pintype "unspecified"))
    )
    (net (code "143") (name "SEN_CH7") (class "Default")
      (node (ref "CN5") (pin "7") (pinfunction "7_7") (pintype "unspecified"))
      (node (ref "U14") (pin "9") (pinfunction "9_9") (pintype "unspecified"))
    )
    (net (code "144") (name "SEN_CH8") (class "Default")
      (node (ref "CN5") (pin "8") (pinfunction "8_8") (pintype "unspecified"))
      (node (ref "K13") (pin "3") (pinfunction "3_3") (pintype "input"))
    )
    (net (code "145") (name "SEN_CH9") (class "Default")
      (node (ref "CN5") (pin "9") (pinfunction "9_9") (pintype "unspecified"))
      (node (ref "K12") (pin "6") (pinfunction "6_6") (pintype "input"))
    )
    (net (code "146") (name "SEN_CH10") (class "Default")
      (node (ref "CN5") (pin "10") (pinfunction "10_10") (pintype "unspecified"))
      (node (ref "U14") (pin "12") (pinfunction "12_12") (pintype "unspecified"))
    )
    (net (code "147") (name "SEN_CH11") (class "Default")
      (node (ref "CN5") (pin "11") (pinfunction "11_11") (pintype "unspecified"))
      (node (ref "U14") (pin "13") (pinfunction "13_13") (pintype "unspecified"))
    )
    (net (code "148") (name "SEN_CH12") (class "Default")
      (node (ref "CN5") (pin "12") (pinfunction "12_12") (pintype "unspecified"))
      (node (ref "U14") (pin "14") (pinfunction "14_14") (pintype "unspecified"))
    )
    (net (code "149") (name "SEN_CH13") (class "Default")
      (node (ref "CN5") (pin "13") (pinfunction "13_13") (pintype "unspecified"))
      (node (ref "K12") (pin "3") (pinfunction "3_3") (pintype "input"))
    )
    (net (code "150") (name "SEN_CH14") (class "Default")
      (node (ref "CN5") (pin "14") (pinfunction "14_14") (pintype "unspecified"))
      (node (ref "U14") (pin "16") (pinfunction "16_16") (pintype "unspecified"))
    )
    (net (code "151") (name "SEN_CH15") (class "Default")
      (node (ref "CN5") (pin "15") (pinfunction "15_15") (pintype "unspecified"))
      (node (ref "U14") (pin "17") (pinfunction "17_17") (pintype "unspecified"))
    )
    (net (code "152") (name "SEN_CH16") (class "Default")
      (node (ref "CN5") (pin "16") (pinfunction "16_16") (pintype "unspecified"))
      (node (ref "K11") (pin "3") (pinfunction "3_3") (pintype "input"))
    )
    (net (code "153") (name "SI") (class "Default")
      (node (ref "U12") (pin "22") (pinfunction "SI_22") (pintype "unspecified"))
      (node (ref "U5") (pin "22") (pinfunction "SI_22") (pintype "unspecified"))
      (node (ref "U6") (pin "13") (pinfunction "PA7_13") (pintype "unspecified"))
    )
    (net (code "154") (name "SO") (class "Default")
      (node (ref "U12") (pin "19") (pinfunction "SO_19") (pintype "unspecified"))
      (node (ref "U5") (pin "19") (pinfunction "SO_19") (pintype "unspecified"))
      (node (ref "U6") (pin "12") (pinfunction "PA6_12") (pintype "unspecified"))
    )
    (net (code "155") (name "SWCLK") (class "Default")
      (node (ref "CN2") (pin "6") (pinfunction "6_6") (pintype "unspecified"))
      (node (ref "U6") (pin "20") (pinfunction "PA14_20") (pintype "unspecified"))
    )
    (net (code "156") (name "SWDIO") (class "Default")
      (node (ref "CN2") (pin "4") (pinfunction "4_4") (pintype "unspecified"))
      (node (ref "U6") (pin "19") (pinfunction "PA13_19") (pintype "unspecified"))
    )
    (net (code "157") (name "SWO") (class "Default")
      (node (ref "CN2") (pin "8") (pinfunction "8_8") (pintype "unspecified"))
    )
    (net (code "158") (name "SYNC") (class "Default")
      (node (ref "R74") (pin "2") (pinfunction "2_2") (pintype "input"))
      (node (ref "U6") (pin "8") (pinfunction "PA2_8") (pintype "unspecified"))
    )
    (net (code "159") (name "USB_N") (class "Default")
      (node (ref "U6") (pin "17") (pinfunction "PA9[PA11]_17") (pintype "unspecified"))
      (node (ref "USB1") (pin "A7") (pinfunction "DN1_A7") (pintype "unspecified"))
      (node (ref "USB1") (pin "B7") (pinfunction "DN2_B7") (pintype "unspecified"))
    )
    (net (code "160") (name "USB_P") (class "Default")
      (node (ref "U6") (pin "18") (pinfunction "PA10[PA12]_18") (pintype "unspecified"))
      (node (ref "USB1") (pin "A6") (pinfunction "DP1_A6") (pintype "unspecified"))
      (node (ref "USB1") (pin "B6") (pinfunction "DP2_B6") (pintype "unspecified"))
    )
    (net (code "161") (name "VBUS") (class "Default")
      (node (ref "USB1") (pin "A4B9") (pinfunction "VBUS_A4B9") (pintype "unspecified"))
      (node (ref "USB1") (pin "B4A9") (pinfunction "VBUS_B4A9") (pintype "unspecified"))
    )
    (net (code "162") (name "unconnected-(CN2-Pad1)") (class "Default")
      (node (ref "CN2") (pin "1") (pinfunction "1_1") (pintype "unspecified"))
    )
    (net (code "163") (name "unconnected-(CN2-Pad2)") (class "Default")
      (node (ref "CN2") (pin "2") (pinfunction "2_2") (pintype "unspecified"))
    )
    (net (code "164") (name "unconnected-(CN2-Pad9)") (class "Default")
      (node (ref "CN2") (pin "9") (pinfunction "9_9") (pintype "unspecified"))
    )
    (net (code "165") (name "unconnected-(CN2-Pad10)") (class "Default")
      (node (ref "CN2") (pin "10") (pinfunction "10_10") (pintype "unspecified"))
    )
    (net (code "166") (name "unconnected-(CN2-Pad13)") (class "Default")
      (node (ref "CN2") (pin "13") (pinfunction "13_13") (pintype "unspecified"))
    )
    (net (code "167") (name "unconnected-(CN2-Pad14)") (class "Default")
      (node (ref "CN2") (pin "14") (pinfunction "14_14") (pintype "unspecified"))
    )
    (net (code "168") (name "unconnected-(K1-Pad2)") (class "Default")
      (node (ref "K1") (pin "2") (pinfunction "2_2") (pintype "input"))
    )
    (net (code "169") (name "unconnected-(K1-Pad7)") (class "Default")
      (node (ref "K1") (pin "7") (pinfunction "7_7") (pintype "input"))
    )
    (net (code "170") (name "unconnected-(K2-Pad2)") (class "Default")
      (node (ref "K2") (pin "2") (pinfunction "2_2") (pintype "input"))
    )
    (net (code "171") (name "unconnected-(K2-Pad7)") (class "Default")
      (node (ref "K2") (pin "7") (pinfunction "7_7") (pintype "input"))
    )
    (net (code "172") (name "unconnected-(K3-Pad2)") (class "Default")
      (node (ref "K3") (pin "2") (pinfunction "2_2") (pintype "input"))
    )
    (net (code "173") (name "unconnected-(K3-Pad7)") (class "Default")
      (node (ref "K3") (pin "7") (pinfunction "7_7") (pintype "input"))
    )
    (net (code "174") (name "unconnected-(K4-Pad2)") (class "Default")
      (node (ref "K4") (pin "2") (pinfunction "2_2") (pintype "input"))
    )
    (net (code "175") (name "unconnected-(K4-Pad7)") (class "Default")
      (node (ref "K4") (pin "7") (pinfunction "7_7") (pintype "input"))
    )
    (net (code "176") (name "unconnected-(K5-Pad2)") (class "Default")
      (node (ref "K5") (pin "2") (pinfunction "2_2") (pintype "input"))
    )
    (net (code "177") (name "unconnected-(K5-Pad7)") (class "Default")
      (node (ref "K5") (pin "7") (pinfunction "7_7") (pintype "input"))
    )
    (net (code "178") (name "unconnected-(K6-Pad2)") (class "Default")
      (node (ref "K6") (pin "2") (pinfunction "2_2") (pintype "input"))
    )
    (net (code "179") (name "unconnected-(K6-Pad7)") (class "Default")
      (node (ref "K6") (pin "7") (pinfunction "7_7") (pintype "input"))
    )
    (net (code "180") (name "unconnected-(K7-Pad2)") (class "Default")
      (node (ref "K7") (pin "2") (pinfunction "2_2") (pintype "input"))
    )
    (net (code "181") (name "unconnected-(K7-Pad7)") (class "Default")
      (node (ref "K7") (pin "7") (pinfunction "7_7") (pintype "input"))
    )
    (net (code "182") (name "unconnected-(U1-DNC-Pad7)") (class "Default")
      (node (ref "U1") (pin "7") (pinfunction "DNC_7") (pintype "unspecified"))
    )
    (net (code "183") (name "unconnected-(U1-NC-Pad3)") (class "Default")
      (node (ref "U1") (pin "3") (pinfunction "NC_3") (pintype "unspecified"))
    )
    (net (code "184") (name "unconnected-(U2-PG-Pad4)") (class "Default")
      (node (ref "U2") (pin "4") (pinfunction "PG_4") (pintype "unspecified+no_connect"))
    )
    (net (code "185") (name "unconnected-(U3-DNC-Pad7)") (class "Default")
      (node (ref "U3") (pin "7") (pinfunction "DNC_7") (pintype "unspecified"))
    )
    (net (code "186") (name "unconnected-(U3-NC-Pad3)") (class "Default")
      (node (ref "U3") (pin "3") (pinfunction "NC_3") (pintype "unspecified"))
    )
    (net (code "187") (name "unconnected-(U4-N{slash}C-Pad4)") (class "Default")
      (node (ref "U4") (pin "4") (pinfunction "N/C_4") (pintype "unspecified+no_connect"))
    )
    (net (code "188") (name "unconnected-(U6-PA0-Pad6)") (class "Default")
      (node (ref "U6") (pin "6") (pinfunction "PA0_6") (pintype "unspecified+no_connect"))
    )
    (net (code "189") (name "unconnected-(U6-PA1-Pad7)") (class "Default")
      (node (ref "U6") (pin "7") (pinfunction "PA1_7") (pintype "unspecified+no_connect"))
    )
    (net (code "190") (name "unconnected-(U9--IND-Pad13)") (class "Default")
      (node (ref "U9") (pin "13") (pinfunction "-IND_13") (pintype "unspecified"))
    )
    (net (code "191") (name "unconnected-(U12-OUT6-Pad8)") (class "Default")
      (node (ref "U12") (pin "8") (pinfunction "OUT6_8") (pintype "unspecified"))
    )
    (net (code "192") (name "unconnected-(U12-OUT7-Pad9)") (class "Default")
      (node (ref "U12") (pin "9") (pinfunction "OUT7_9") (pintype "unspecified"))
    )
    (net (code "193") (name "unconnected-(U12-OUT8-Pad10)") (class "Default")
      (node (ref "U12") (pin "10") (pinfunction "OUT8_10") (pintype "unspecified"))
    )
    (net (code "194") (name "unconnected-(U14-Pad23)") (class "Default")
      (node (ref "U14") (pin "23") (pinfunction "23_23") (pintype "unspecified"))
    )
    (net (code "195") (name "unconnected-(U14-Pad25)") (class "Default")
      (node (ref "U14") (pin "25") (pinfunction "25_25") (pintype "unspecified"))
    )
    (net (code "196") (name "unconnected-(U14-Pad26)") (class "Default")
      (node (ref "U14") (pin "26") (pinfunction "26_26") (pintype "unspecified"))
    )
    (net (code "197") (name "unconnected-(U14-Pad27)") (class "Default")
      (node (ref "U14") (pin "27") (pinfunction "27_27") (pintype "unspecified"))
    )
    (net (code "198") (name "unconnected-(U14-Pad28)") (class "Default")
      (node (ref "U14") (pin "28") (pinfunction "28_28") (pintype "unspecified"))
    )
    (net (code "199") (name "unconnected-(U14-Pad29)") (class "Default")
      (node (ref "U14") (pin "29") (pinfunction "29_29") (pintype "unspecified"))
    )
    (net (code "200") (name "unconnected-(U14-Pad30)") (class "Default")
      (node (ref "U14") (pin "30") (pinfunction "30_30") (pintype "unspecified"))
    )
    (net (code "201") (name "unconnected-(U14-Pad31)") (class "Default")
      (node (ref "U14") (pin "31") (pinfunction "31_31") (pintype "unspecified"))
    )
    (net (code "202") (name "unconnected-(U14-Pad32)") (class "Default")
      (node (ref "U14") (pin "32") (pinfunction "32_32") (pintype "unspecified"))
    )
    (net (code "203") (name "unconnected-(U14-Pad33)") (class "Default")
      (node (ref "U14") (pin "33") (pinfunction "33_33") (pintype "unspecified"))
    )
    (net (code "204") (name "unconnected-(U14-Pad34)") (class "Default")
      (node (ref "U14") (pin "34") (pinfunction "34_34") (pintype "unspecified"))
    )
    (net (code "205") (name "unconnected-(USB1-SBU1-PadA8)") (class "Default")
      (node (ref "USB1") (pin "A8") (pinfunction "SBU1_A8") (pintype "unspecified+no_connect"))
    )
    (net (code "206") (name "unconnected-(USB1-SBU2-PadB8)") (class "Default")
      (node (ref "USB1") (pin "B8") (pinfunction "SBU2_B8") (pintype "unspecified+no_connect"))
    )
    (net (code "207") (name "unconnected-(X1-GND-Pad2)") (class "Default")
      (node (ref "X1") (pin "2") (pinfunction "GND_2") (pintype "input"))
    )
    (net (code "208") (name "unconnected-(X1-GND-Pad4)") (class "Default")
      (node (ref "X1") (pin "4") (pinfunction "GND_4") (pintype "input"))
    )
  )
)
